# axiom_beta_plugin_module_TE0714_SDI_v0_5.net
KiCad netlist of a schematic drawn in EAGLE
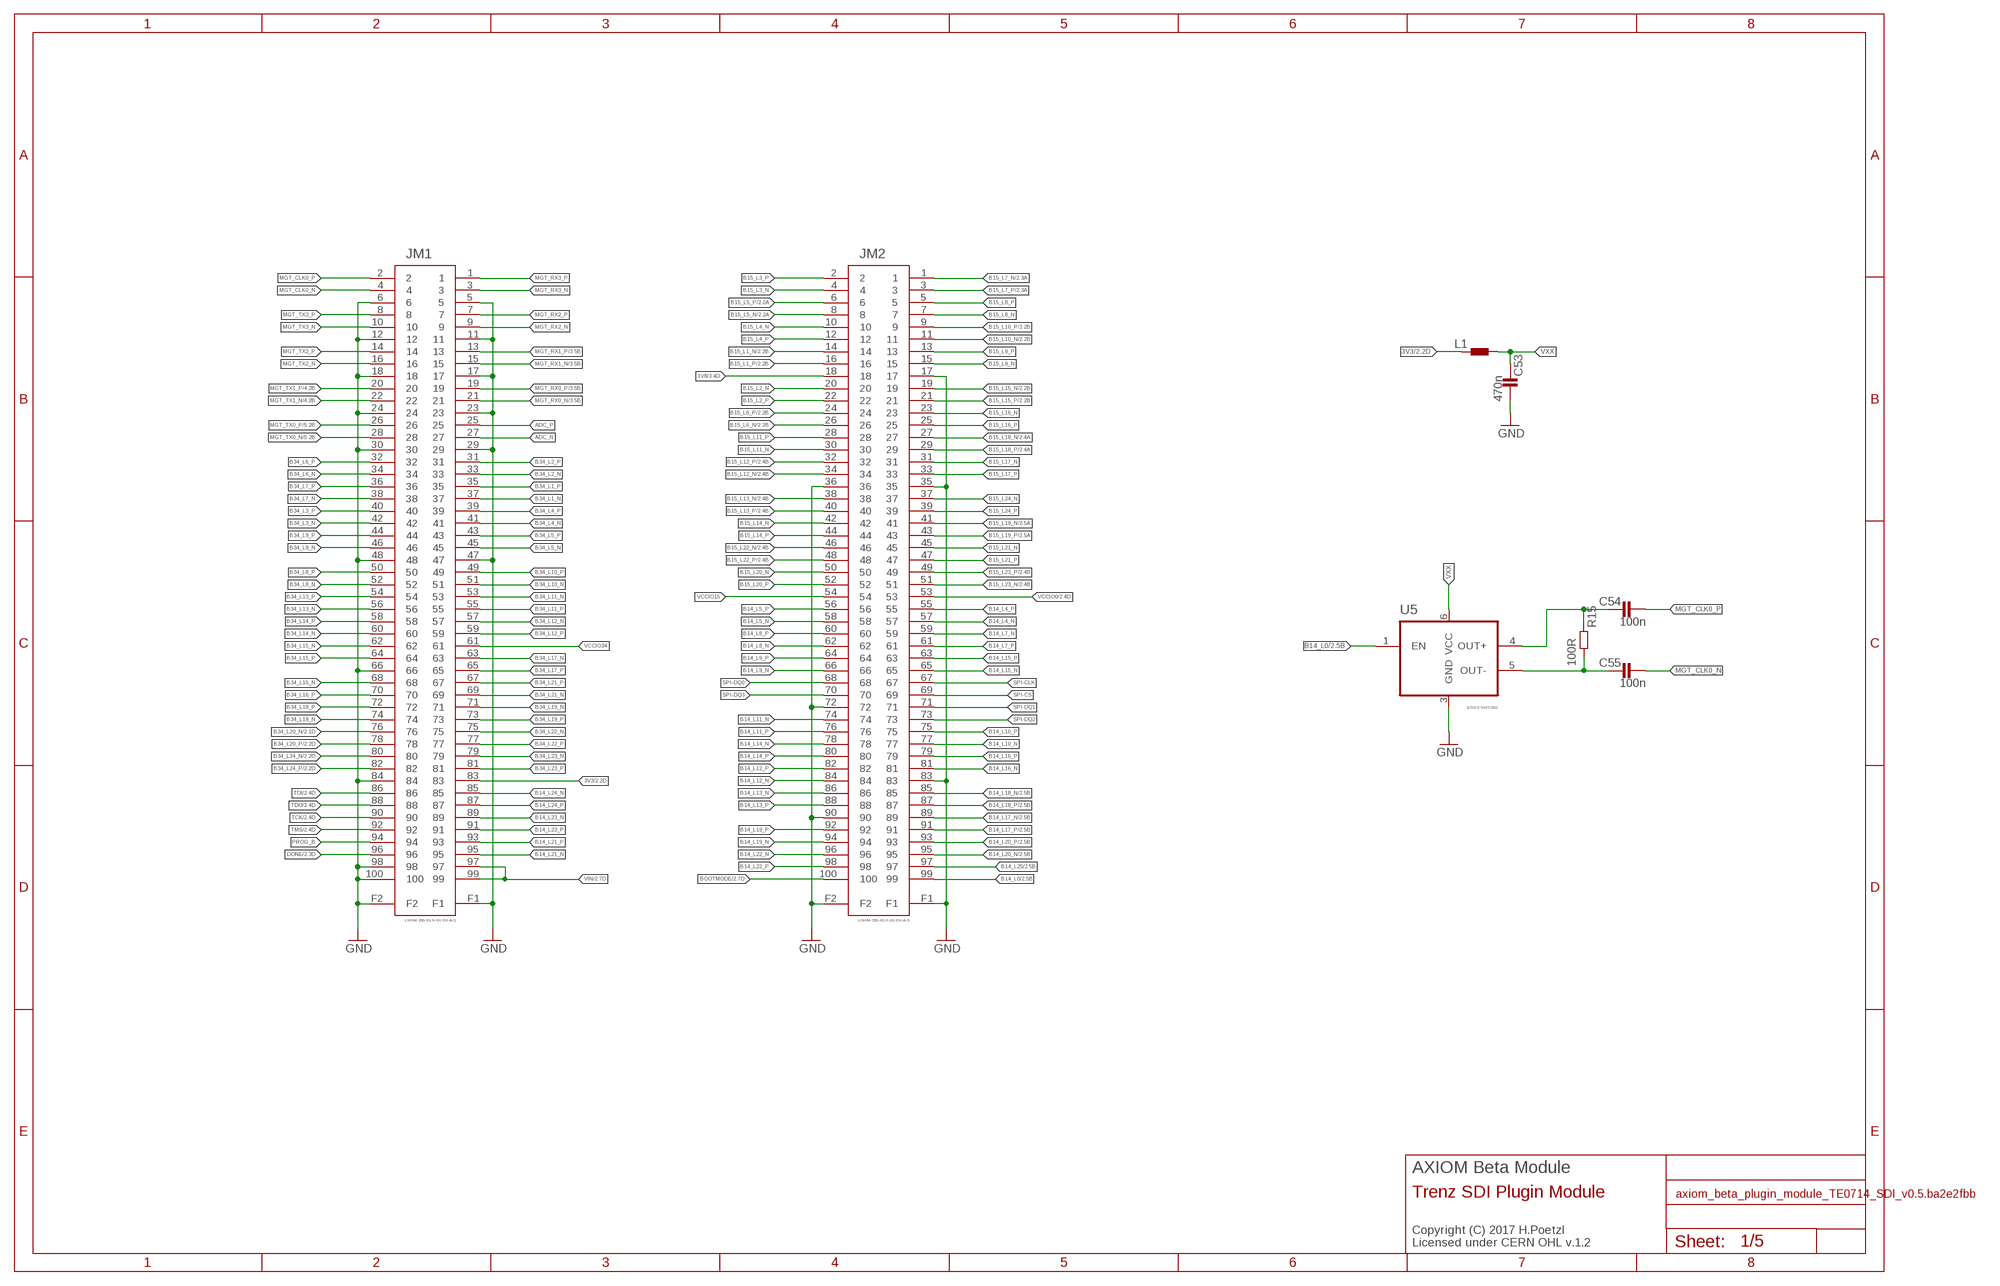
[diagram p0: schematic, sheet 1]
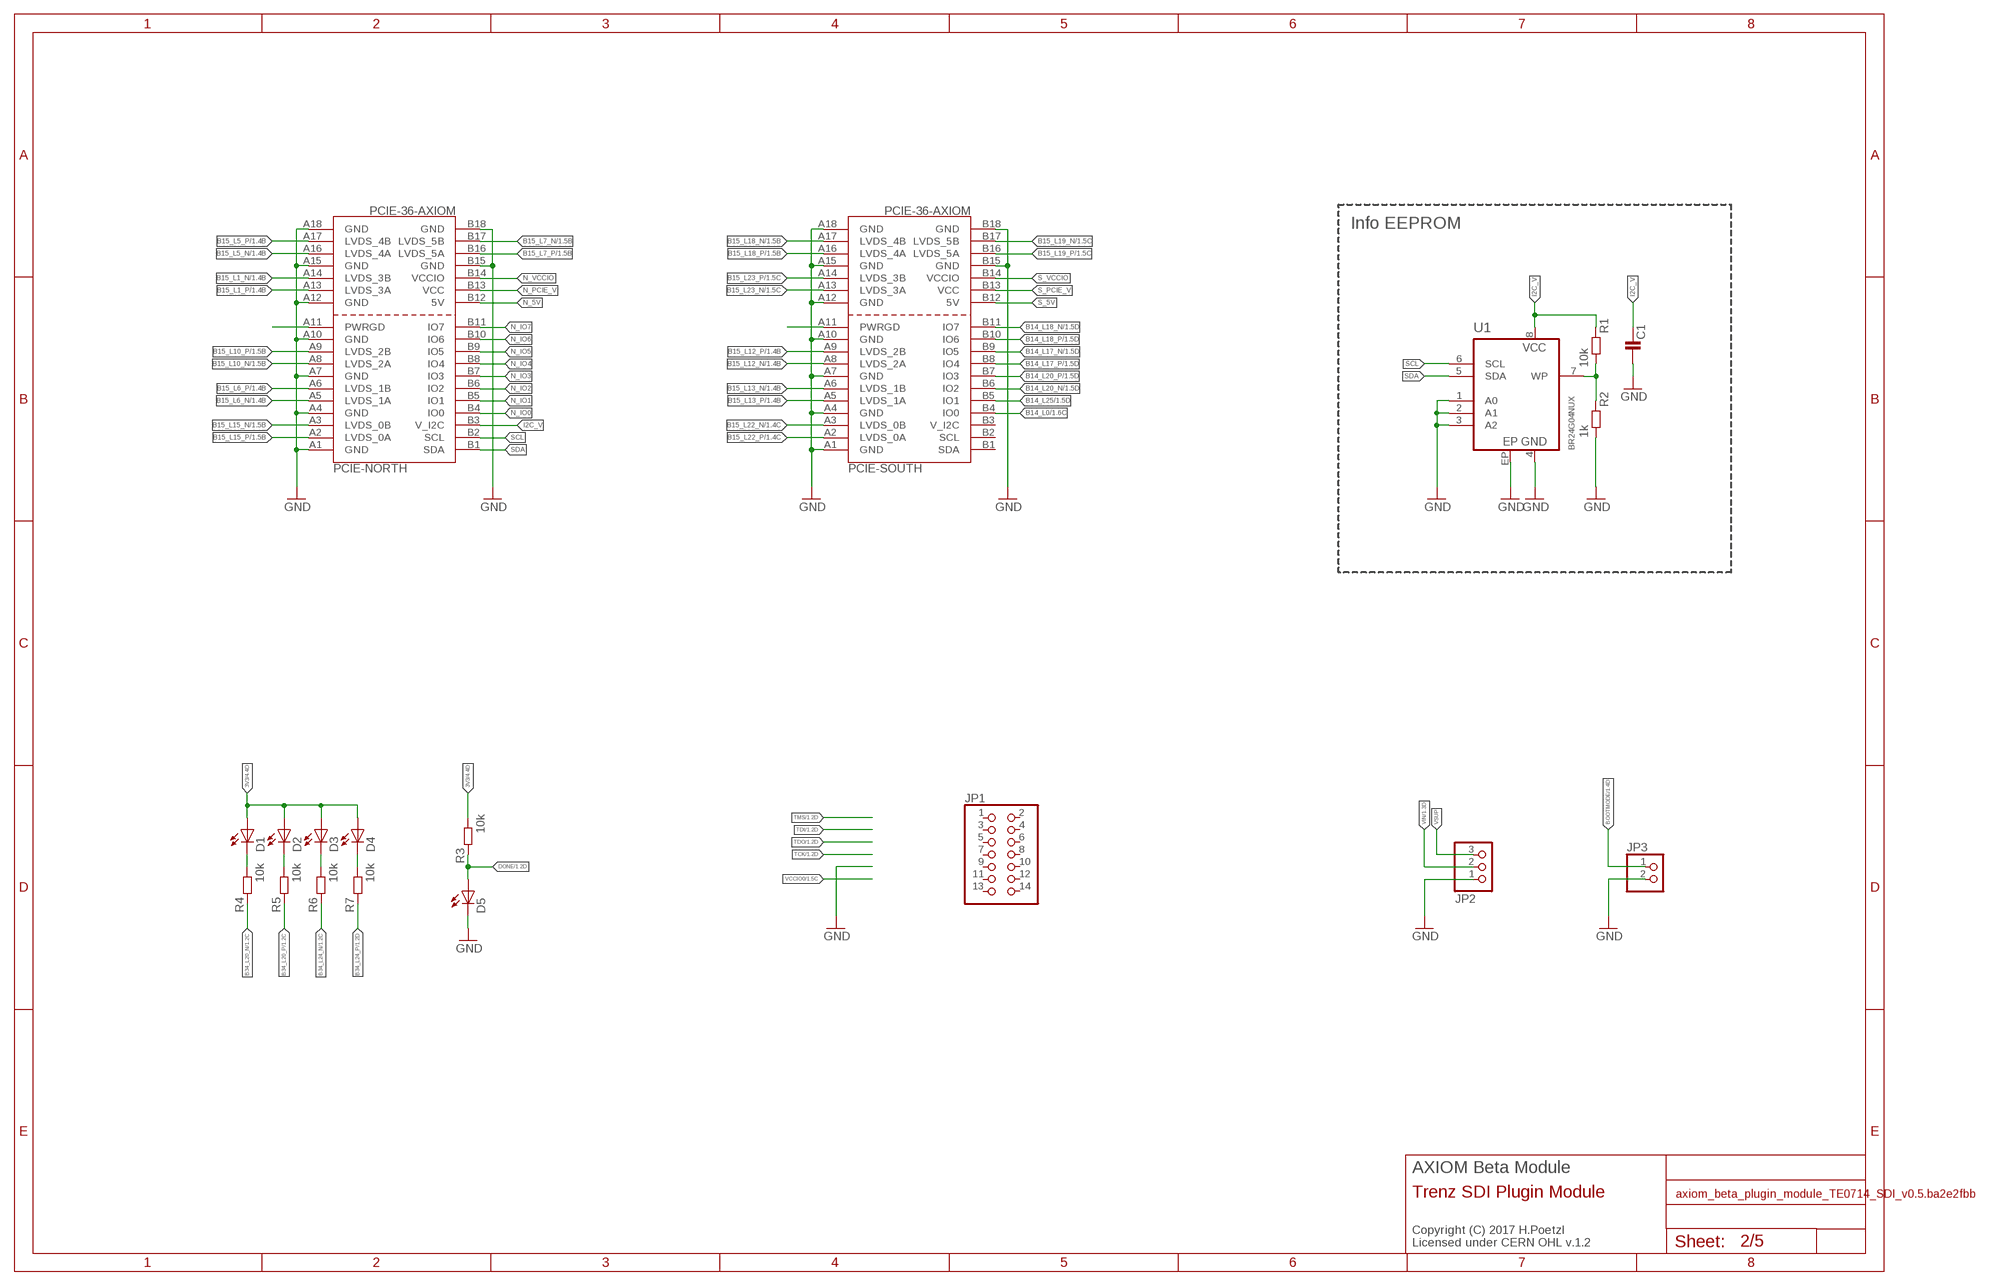
[diagram p1: schematic, sheet 2]
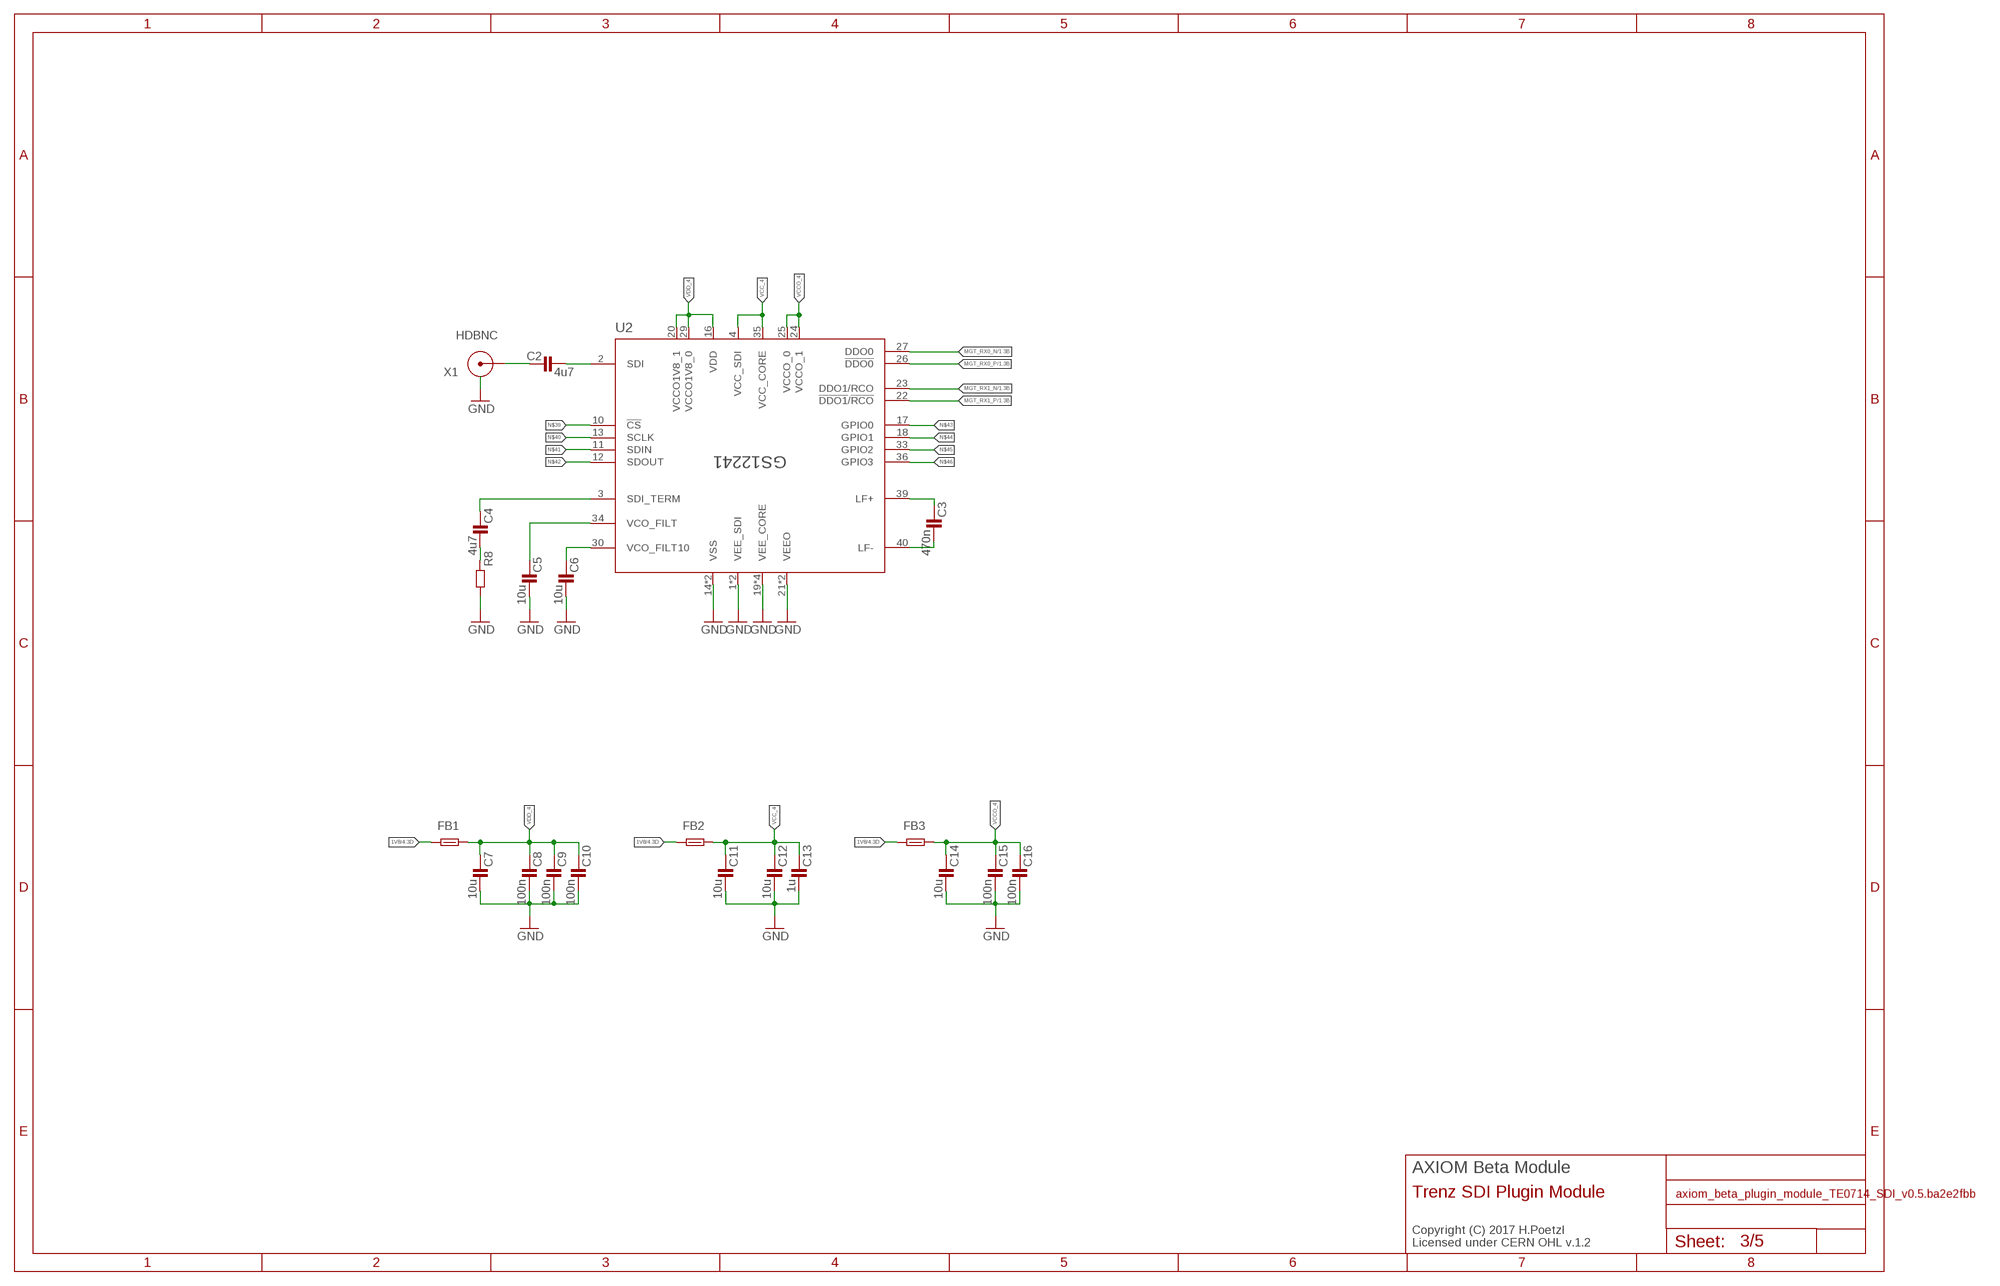
[diagram p2: schematic, sheet 3]
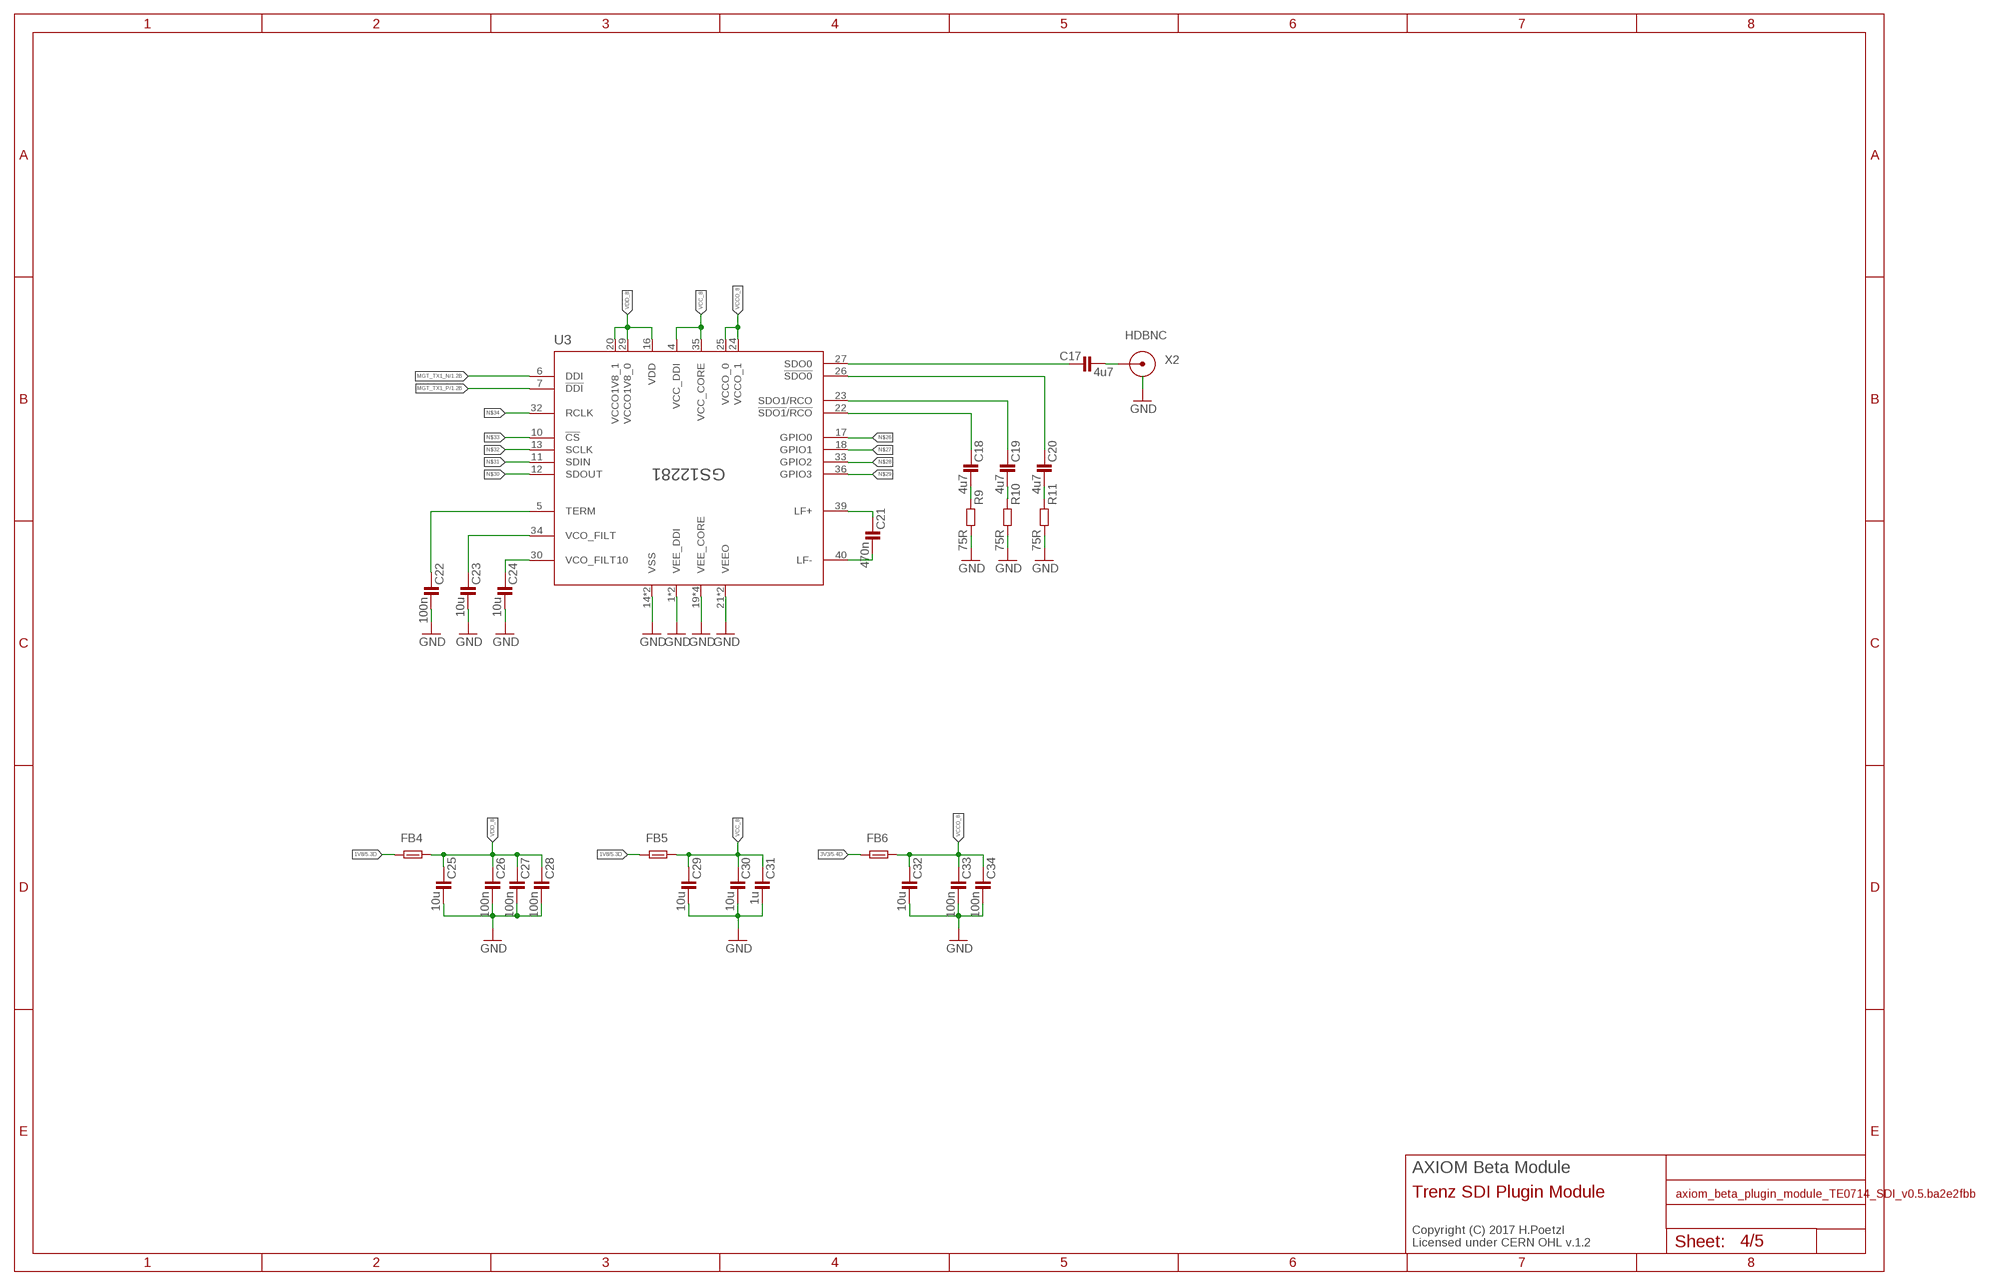
[diagram p3: schematic, sheet 4]
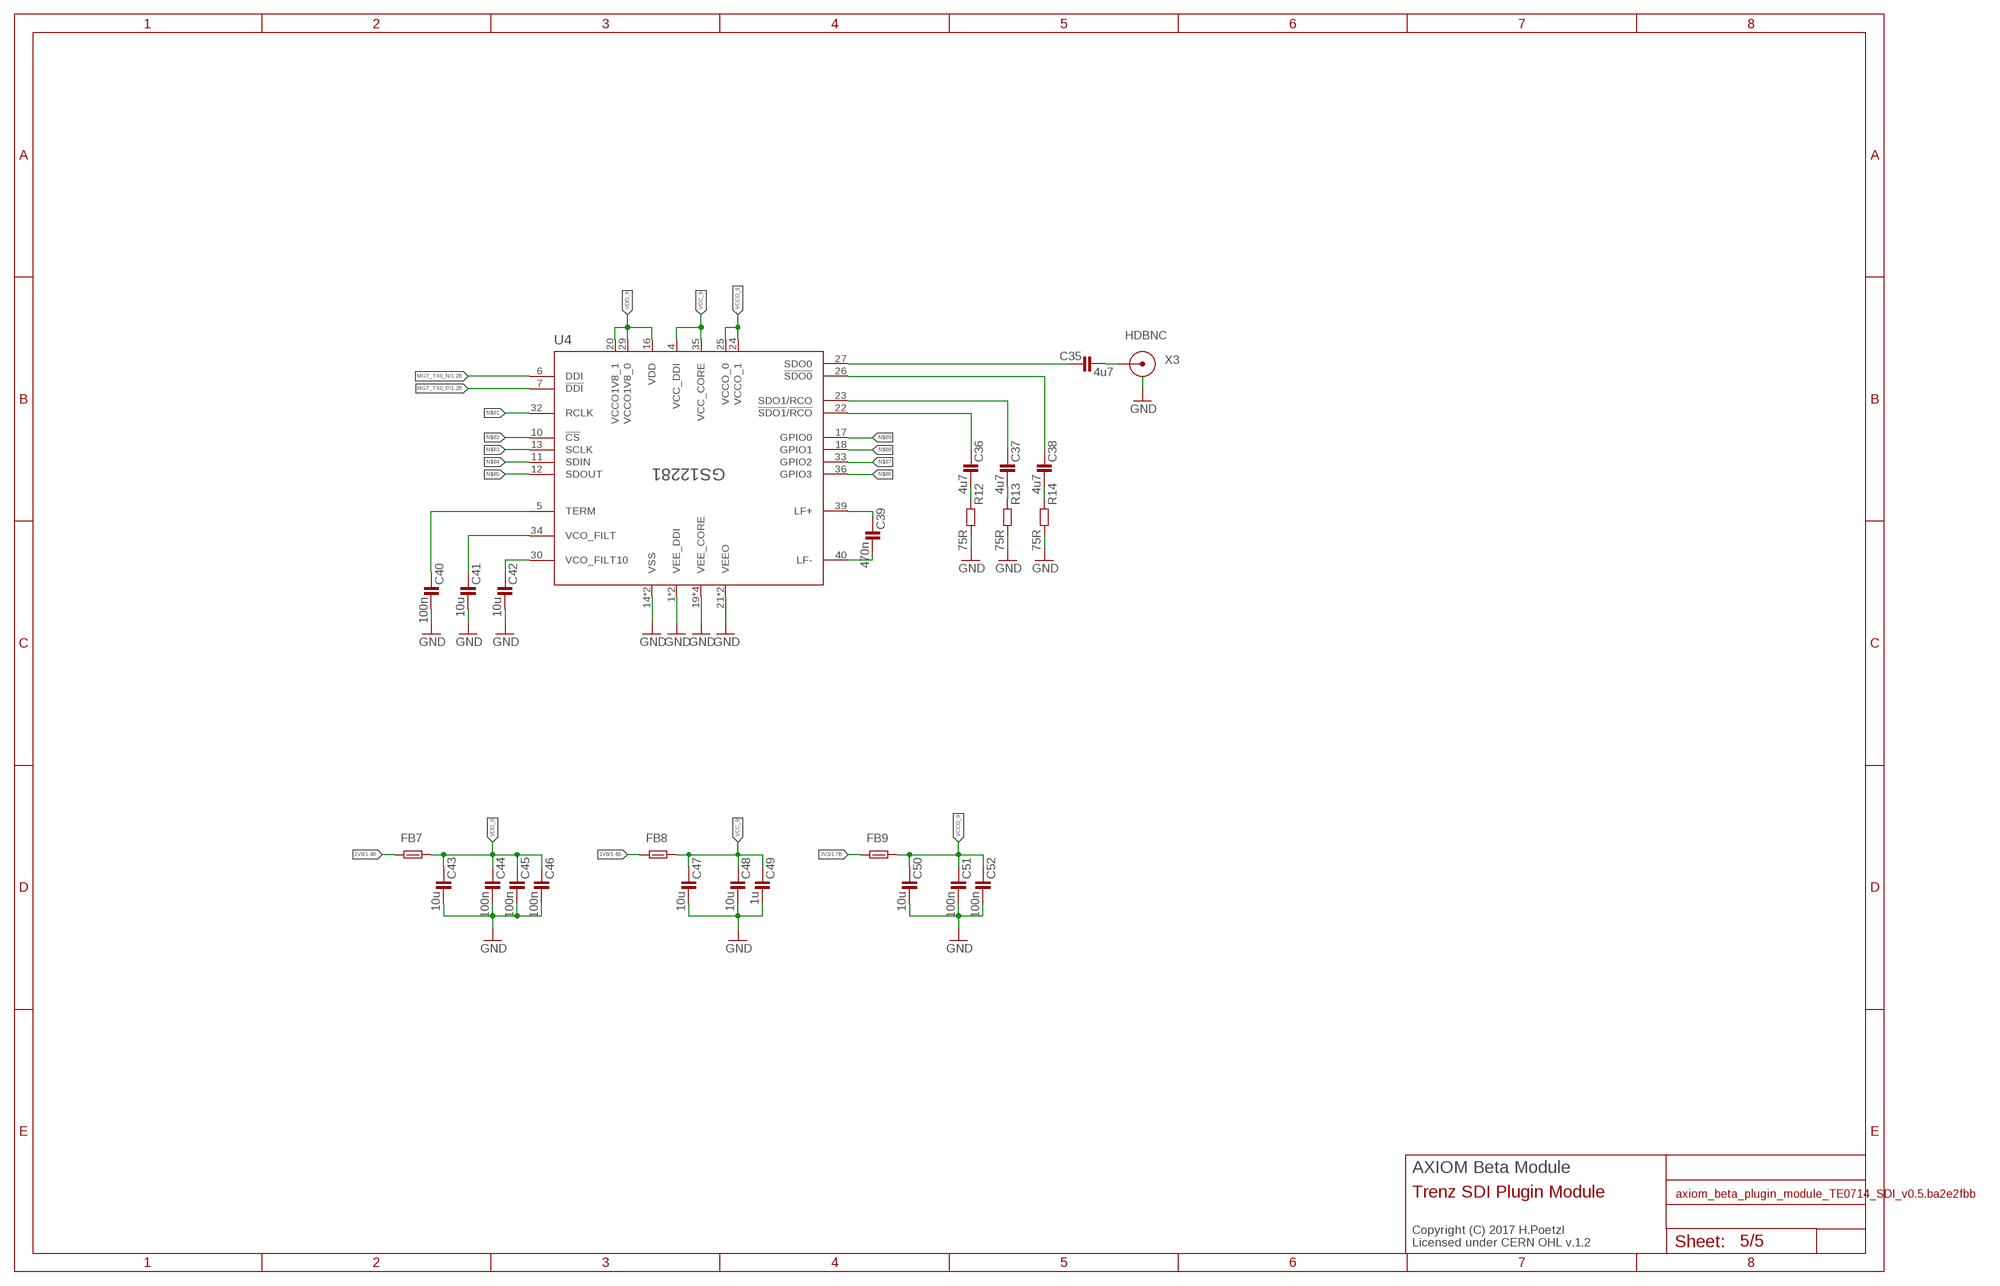
[diagram p4: schematic, sheet 5]

(export (version "E")
  (design (tool "Eeschema 10.0.6"))
  (components
    (comp (ref "C2")
      (value "4u7")
      (footprint "eagle-import:0402-C")
      (libsource (lib "eagle-import") (part "C0402-C"))
    )
    (comp (ref "C3")
      (value "470n")
      (footprint "eagle-import:0201-C")
      (libsource (lib "eagle-import") (part "C0201-C"))
    )
    (comp (ref "C4")
      (value "4u7")
      (footprint "eagle-import:0201-C")
      (libsource (lib "eagle-import") (part "C0201-C"))
    )
    (comp (ref "C5")
      (value "10u")
      (footprint "eagle-import:0201-C")
      (libsource (lib "eagle-import") (part "C0201-C"))
    )
    (comp (ref "C6")
      (value "10u")
      (footprint "eagle-import:0201-C")
      (libsource (lib "eagle-import") (part "C0201-C"))
    )
    (comp (ref "C7")
      (value "10u")
      (footprint "eagle-import:0402-C")
      (libsource (lib "eagle-import") (part "C0402-C"))
    )
    (comp (ref "C8")
      (value "100n")
      (footprint "eagle-import:0201-C")
      (libsource (lib "eagle-import") (part "C0201-C"))
    )
    (comp (ref "C9")
      (value "100n")
      (footprint "eagle-import:0201-C")
      (libsource (lib "eagle-import") (part "C0201-C"))
    )
    (comp (ref "C10")
      (value "100n")
      (footprint "eagle-import:0201-C")
      (libsource (lib "eagle-import") (part "C0201-C"))
    )
    (comp (ref "C11")
      (value "10u")
      (footprint "eagle-import:0402-C")
      (libsource (lib "eagle-import") (part "C0402-C"))
    )
    (comp (ref "C12")
      (value "10u")
      (footprint "eagle-import:0201-C")
      (libsource (lib "eagle-import") (part "C0201-C"))
    )
    (comp (ref "C13")
      (value "1u")
      (footprint "eagle-import:0201-C")
      (libsource (lib "eagle-import") (part "C0201-C"))
    )
    (comp (ref "C14")
      (value "10u")
      (footprint "eagle-import:0402-C")
      (libsource (lib "eagle-import") (part "C0402-C"))
    )
    (comp (ref "C15")
      (value "100n")
      (footprint "eagle-import:0201-C")
      (libsource (lib "eagle-import") (part "C0201-C"))
    )
    (comp (ref "C16")
      (value "100n")
      (footprint "eagle-import:0201-C")
      (libsource (lib "eagle-import") (part "C0201-C"))
    )
    (comp (ref "FB1")
      (value "FB0402-C")
      (footprint "eagle-import:0402-C")
      (libsource (lib "eagle-import") (part "FB0402-C"))
    )
    (comp (ref "FB2")
      (value "FB0402-C")
      (footprint "eagle-import:0402-C")
      (libsource (lib "eagle-import") (part "FB0402-C"))
    )
    (comp (ref "FB3")
      (value "FB0402-C")
      (footprint "eagle-import:0402-C")
      (libsource (lib "eagle-import") (part "FB0402-C"))
    )
    (comp (ref "R8")
      (value "R0201-C")
      (footprint "eagle-import:0201-C")
      (libsource (lib "eagle-import") (part "R0201-C"))
    )
    (comp (ref "U2")
      (value "GS12241")
      (footprint "eagle-import:UQFN40P600X400X100-41N")
      (libsource (lib "eagle-import") (part "GS12241"))
    )
    (comp (ref "X1")
      (value "HDBNC")
      (footprint "eagle-import:HDBNC_EDGE_2SIDE")
      (libsource (lib "eagle-import") (part "HDBNC"))
    )
    (comp (ref "C53")
      (value "470n")
      (footprint "eagle-import:0402-C")
      (libsource (lib "eagle-import") (part "C0402-C"))
    )
    (comp (ref "C54")
      (value "100n")
      (footprint "eagle-import:0201-C")
      (libsource (lib "eagle-import") (part "C0201-C"))
    )
    (comp (ref "C55")
      (value "100n")
      (footprint "eagle-import:0201-C")
      (libsource (lib "eagle-import") (part "C0201-C"))
    )
    (comp (ref "JM1")
      (value "LSHM-150-XX.X-XX-DV-A-S")
      (footprint "eagle-import:LSHM-150-XX.X-XX-DV-A-S")
      (libsource (lib "eagle-import") (part "LSHM-150-XX.X-XX-DV-A-S"))
    )
    (comp (ref "JM2")
      (value "LSHM-150-XX.X-XX-DV-A-S")
      (footprint "eagle-import:LSHM-150-XX.X-XX-DV-A-S")
      (libsource (lib "eagle-import") (part "LSHM-150-XX.X-XX-DV-A-S"))
    )
    (comp (ref "L1")
      (value "L0402-C")
      (footprint "eagle-import:0402-C")
      (libsource (lib "eagle-import") (part "L0402-C"))
    )
    (comp (ref "R15")
      (value "100R")
      (footprint "eagle-import:0201-C")
      (libsource (lib "eagle-import") (part "R0201-C"))
    )
    (comp (ref "U5")
      (value "DSC11XX-3.2X2.5")
      (footprint "eagle-import:3.2X2.5")
      (libsource (lib "eagle-import") (part "DSC11XX-3.2X2.5"))
    )
    (comp (ref "C1")
      (value "C0402-B")
      (footprint "eagle-import:0402-B")
      (libsource (lib "eagle-import") (part "C0402-B"))
    )
    (comp (ref "D1")
      (value "LED")
      (footprint "eagle-import:SMARTLED-TTW")
      (libsource (lib "eagle-import") (part "LED"))
    )
    (comp (ref "D2")
      (value "LED")
      (footprint "eagle-import:SMARTLED-TTW")
      (libsource (lib "eagle-import") (part "LED"))
    )
    (comp (ref "D3")
      (value "LED")
      (footprint "eagle-import:SMARTLED-TTW")
      (libsource (lib "eagle-import") (part "LED"))
    )
    (comp (ref "D4")
      (value "LED")
      (footprint "eagle-import:SMARTLED-TTW")
      (libsource (lib "eagle-import") (part "LED"))
    )
    (comp (ref "D5")
      (value "LED")
      (footprint "eagle-import:SMARTLED-TTW")
      (libsource (lib "eagle-import") (part "LED"))
    )
    (comp (ref "JP1")
      (value "PINHD-2X07_2.00")
      (footprint "eagle-import:2X07M")
      (libsource (lib "eagle-import") (part "PINHD-2X07_2.00"))
    )
    (comp (ref "JP2")
      (value "PINHD-1X03_2.54-90°-S")
      (footprint "eagle-import:1X03_90-S")
      (libsource (lib "eagle-import") (part "PINHD-1X03_2.54-90°-S"))
    )
    (comp (ref "JP3")
      (value "PINHD-1X02_2.54-S")
      (footprint "eagle-import:1X02-S")
      (libsource (lib "eagle-import") (part "PINHD-1X02_2.54-S"))
    )
    (comp (ref "PCIE-NORTH")
      (value "PCIE-36-AXIOM")
      (footprint "eagle-import:PCIE-36-AXIOM")
      (libsource (lib "eagle-import") (part "PCIE-36-AXIOM"))
    )
    (comp (ref "PCIE-SOUTH")
      (value "PCIE-36-AXIOM")
      (footprint "eagle-import:PCIE-36-AXIOM")
      (libsource (lib "eagle-import") (part "PCIE-36-AXIOM"))
    )
    (comp (ref "R1")
      (value "10k")
      (footprint "eagle-import:0402-B")
      (libsource (lib "eagle-import") (part "R0402-B"))
    )
    (comp (ref "R2")
      (value "1k")
      (footprint "eagle-import:0402-B")
      (libsource (lib "eagle-import") (part "R0402-B"))
    )
    (comp (ref "R3")
      (value "10k")
      (footprint "eagle-import:0402-C")
      (libsource (lib "eagle-import") (part "R0402-C"))
    )
    (comp (ref "R4")
      (value "10k")
      (footprint "eagle-import:0402-C")
      (libsource (lib "eagle-import") (part "R0402-C"))
    )
    (comp (ref "R5")
      (value "10k")
      (footprint "eagle-import:0402-C")
      (libsource (lib "eagle-import") (part "R0402-C"))
    )
    (comp (ref "R6")
      (value "10k")
      (footprint "eagle-import:0402-C")
      (libsource (lib "eagle-import") (part "R0402-C"))
    )
    (comp (ref "R7")
      (value "10k")
      (footprint "eagle-import:0402-C")
      (libsource (lib "eagle-import") (part "R0402-C"))
    )
    (comp (ref "U1")
      (value "BR24G04NUX")
      (footprint "eagle-import:DFN200X300X100-9N")
      (libsource (lib "eagle-import") (part "BR24G04NUX"))
    )
    (comp (ref "C35")
      (value "4u7")
      (footprint "eagle-import:0402-C")
      (libsource (lib "eagle-import") (part "C0402-C"))
    )
    (comp (ref "C36")
      (value "4u7")
      (footprint "eagle-import:0201-C")
      (libsource (lib "eagle-import") (part "C0201-C"))
    )
    (comp (ref "C37")
      (value "4u7")
      (footprint "eagle-import:0201-C")
      (libsource (lib "eagle-import") (part "C0201-C"))
    )
    (comp (ref "C38")
      (value "4u7")
      (footprint "eagle-import:0201-C")
      (libsource (lib "eagle-import") (part "C0201-C"))
    )
    (comp (ref "C39")
      (value "470n")
      (footprint "eagle-import:0201-C")
      (libsource (lib "eagle-import") (part "C0201-C"))
    )
    (comp (ref "C40")
      (value "100n")
      (footprint "eagle-import:0201-C")
      (libsource (lib "eagle-import") (part "C0201-C"))
    )
    (comp (ref "C41")
      (value "10u")
      (footprint "eagle-import:0201-C")
      (libsource (lib "eagle-import") (part "C0201-C"))
    )
    (comp (ref "C42")
      (value "10u")
      (footprint "eagle-import:0201-C")
      (libsource (lib "eagle-import") (part "C0201-C"))
    )
    (comp (ref "C43")
      (value "10u")
      (footprint "eagle-import:0402-C")
      (libsource (lib "eagle-import") (part "C0402-C"))
    )
    (comp (ref "C44")
      (value "100n")
      (footprint "eagle-import:0201-C")
      (libsource (lib "eagle-import") (part "C0201-C"))
    )
    (comp (ref "C45")
      (value "100n")
      (footprint "eagle-import:0201-C")
      (libsource (lib "eagle-import") (part "C0201-C"))
    )
    (comp (ref "C46")
      (value "100n")
      (footprint "eagle-import:0201-C")
      (libsource (lib "eagle-import") (part "C0201-C"))
    )
    (comp (ref "C47")
      (value "10u")
      (footprint "eagle-import:0402-C")
      (libsource (lib "eagle-import") (part "C0402-C"))
    )
    (comp (ref "C48")
      (value "10u")
      (footprint "eagle-import:0201-C")
      (libsource (lib "eagle-import") (part "C0201-C"))
    )
    (comp (ref "C49")
      (value "1u")
      (footprint "eagle-import:0201-C")
      (libsource (lib "eagle-import") (part "C0201-C"))
    )
    (comp (ref "C50")
      (value "10u")
      (footprint "eagle-import:0402-C")
      (libsource (lib "eagle-import") (part "C0402-C"))
    )
    (comp (ref "C51")
      (value "100n")
      (footprint "eagle-import:0201-C")
      (libsource (lib "eagle-import") (part "C0201-C"))
    )
    (comp (ref "C52")
      (value "100n")
      (footprint "eagle-import:0201-C")
      (libsource (lib "eagle-import") (part "C0201-C"))
    )
    (comp (ref "FB7")
      (value "FB0402-C")
      (footprint "eagle-import:0402-C")
      (libsource (lib "eagle-import") (part "FB0402-C"))
    )
    (comp (ref "FB8")
      (value "FB0402-C")
      (footprint "eagle-import:0402-C")
      (libsource (lib "eagle-import") (part "FB0402-C"))
    )
    (comp (ref "FB9")
      (value "FB0402-C")
      (footprint "eagle-import:0402-C")
      (libsource (lib "eagle-import") (part "FB0402-C"))
    )
    (comp (ref "R12")
      (value "75R")
      (footprint "eagle-import:0201-C")
      (libsource (lib "eagle-import") (part "R0201-C"))
    )
    (comp (ref "R13")
      (value "75R")
      (footprint "eagle-import:0201-C")
      (libsource (lib "eagle-import") (part "R0201-C"))
    )
    (comp (ref "R14")
      (value "75R")
      (footprint "eagle-import:0201-C")
      (libsource (lib "eagle-import") (part "R0201-C"))
    )
    (comp (ref "U4")
      (value "GS12281")
      (footprint "eagle-import:UQFN40P600X400X100-41N")
      (libsource (lib "eagle-import") (part "GS12281"))
    )
    (comp (ref "X3")
      (value "HDBNC")
      (footprint "eagle-import:HDBNC_EDGE_2SIDE")
      (libsource (lib "eagle-import") (part "HDBNC"))
    )
    (comp (ref "C17")
      (value "4u7")
      (footprint "eagle-import:0402-C")
      (libsource (lib "eagle-import") (part "C0402-C"))
    )
    (comp (ref "C18")
      (value "4u7")
      (footprint "eagle-import:0201-C")
      (libsource (lib "eagle-import") (part "C0201-C"))
    )
    (comp (ref "C19")
      (value "4u7")
      (footprint "eagle-import:0201-C")
      (libsource (lib "eagle-import") (part "C0201-C"))
    )
    (comp (ref "C20")
      (value "4u7")
      (footprint "eagle-import:0201-C")
      (libsource (lib "eagle-import") (part "C0201-C"))
    )
    (comp (ref "C21")
      (value "470n")
      (footprint "eagle-import:0201-C")
      (libsource (lib "eagle-import") (part "C0201-C"))
    )
    (comp (ref "C22")
      (value "100n")
      (footprint "eagle-import:0201-C")
      (libsource (lib "eagle-import") (part "C0201-C"))
    )
    (comp (ref "C23")
      (value "10u")
      (footprint "eagle-import:0201-C")
      (libsource (lib "eagle-import") (part "C0201-C"))
    )
    (comp (ref "C24")
      (value "10u")
      (footprint "eagle-import:0201-C")
      (libsource (lib "eagle-import") (part "C0201-C"))
    )
    (comp (ref "C25")
      (value "10u")
      (footprint "eagle-import:0402-C")
      (libsource (lib "eagle-import") (part "C0402-C"))
    )
    (comp (ref "C26")
      (value "100n")
      (footprint "eagle-import:0201-C")
      (libsource (lib "eagle-import") (part "C0201-C"))
    )
    (comp (ref "C27")
      (value "100n")
      (footprint "eagle-import:0201-C")
      (libsource (lib "eagle-import") (part "C0201-C"))
    )
    (comp (ref "C28")
      (value "100n")
      (footprint "eagle-import:0201-C")
      (libsource (lib "eagle-import") (part "C0201-C"))
    )
    (comp (ref "C29")
      (value "10u")
      (footprint "eagle-import:0402-C")
      (libsource (lib "eagle-import") (part "C0402-C"))
    )
    (comp (ref "C30")
      (value "10u")
      (footprint "eagle-import:0201-C")
      (libsource (lib "eagle-import") (part "C0201-C"))
    )
    (comp (ref "C31")
      (value "1u")
      (footprint "eagle-import:0201-C")
      (libsource (lib "eagle-import") (part "C0201-C"))
    )
    (comp (ref "C32")
      (value "10u")
      (footprint "eagle-import:0402-C")
      (libsource (lib "eagle-import") (part "C0402-C"))
    )
    (comp (ref "C33")
      (value "100n")
      (footprint "eagle-import:0201-C")
      (libsource (lib "eagle-import") (part "C0201-C"))
    )
    (comp (ref "C34")
      (value "100n")
      (footprint "eagle-import:0201-C")
      (libsource (lib "eagle-import") (part "C0201-C"))
    )
    (comp (ref "FB4")
      (value "FB0402-C")
      (footprint "eagle-import:0402-C")
      (libsource (lib "eagle-import") (part "FB0402-C"))
    )
    (comp (ref "FB5")
      (value "FB0402-C")
      (footprint "eagle-import:0402-C")
      (libsource (lib "eagle-import") (part "FB0402-C"))
    )
    (comp (ref "FB6")
      (value "FB0402-C")
      (footprint "eagle-import:0402-C")
      (libsource (lib "eagle-import") (part "FB0402-C"))
    )
    (comp (ref "R9")
      (value "75R")
      (footprint "eagle-import:0201-C")
      (libsource (lib "eagle-import") (part "R0201-C"))
    )
    (comp (ref "R10")
      (value "75R")
      (footprint "eagle-import:0201-C")
      (libsource (lib "eagle-import") (part "R0201-C"))
    )
    (comp (ref "R11")
      (value "75R")
      (footprint "eagle-import:0201-C")
      (libsource (lib "eagle-import") (part "R0201-C"))
    )
    (comp (ref "U3")
      (value "GS12281")
      (footprint "eagle-import:UQFN40P600X400X100-41N")
      (libsource (lib "eagle-import") (part "GS12281"))
    )
    (comp (ref "X2")
      (value "HDBNC")
      (footprint "eagle-import:HDBNC_EDGE_2SIDE")
      (libsource (lib "eagle-import") (part "HDBNC"))
    )
  )
  (nets
    (net (code "1") (name "1V8") (class "Default")
      (node (ref "FB1") (pin "1") (pinfunction "1_1") (pintype "passive"))
      (node (ref "FB2") (pin "1") (pinfunction "1_1") (pintype "passive"))
      (node (ref "FB3") (pin "1") (pinfunction "1_1") (pintype "passive"))
      (node (ref "FB4") (pin "1") (pinfunction "1_1") (pintype "passive"))
      (node (ref "FB5") (pin "1") (pinfunction "1_1") (pintype "passive"))
      (node (ref "FB7") (pin "1") (pinfunction "1_1") (pintype "passive"))
      (node (ref "FB8") (pin "1") (pinfunction "1_1") (pintype "passive"))
      (node (ref "JM2") (pin "18") (pinfunction "18_18") (pintype "bidirectional"))
    )
    (net (code "2") (name "3V3") (class "Default")
      (node (ref "D1") (pin "A@1") (pinfunction "A_A@1") (pintype "passive"))
      (node (ref "D2") (pin "A@1") (pinfunction "A_A@1") (pintype "passive"))
      (node (ref "D3") (pin "A@1") (pinfunction "A_A@1") (pintype "passive"))
      (node (ref "D4") (pin "A@1") (pinfunction "A_A@1") (pintype "passive"))
      (node (ref "FB6") (pin "1") (pinfunction "1_1") (pintype "passive"))
      (node (ref "FB9") (pin "1") (pinfunction "1_1") (pintype "passive"))
      (node (ref "JM1") (pin "83") (pinfunction "83_83") (pintype "bidirectional"))
      (node (ref "L1") (pin "1") (pinfunction "1_1") (pintype "passive"))
      (node (ref "R3") (pin "2") (pinfunction "2_2") (pintype "passive"))
    )
    (net (code "3") (name "ADC_N") (class "Default")
      (node (ref "JM1") (pin "27") (pinfunction "27_27") (pintype "bidirectional"))
    )
    (net (code "4") (name "ADC_P") (class "Default")
      (node (ref "JM1") (pin "25") (pinfunction "25_25") (pintype "bidirectional"))
    )
    (net (code "5") (name "B14_L0") (class "Default")
      (node (ref "JM2") (pin "99") (pinfunction "99_99") (pintype "bidirectional"))
      (node (ref "PCIE-SOUTH") (pin "B4") (pinfunction "IO0_B4") (pintype "passive"))
      (node (ref "U5") (pin "1") (pinfunction "EN_1") (pintype "input"))
    )
    (net (code "6") (name "B14_L4_N") (class "Default")
      (node (ref "JM2") (pin "57") (pinfunction "57_57") (pintype "bidirectional"))
    )
    (net (code "7") (name "B14_L4_P") (class "Default")
      (node (ref "JM2") (pin "55") (pinfunction "55_55") (pintype "bidirectional"))
    )
    (net (code "8") (name "B14_L5_N") (class "Default")
      (node (ref "JM2") (pin "58") (pinfunction "58_58") (pintype "bidirectional"))
    )
    (net (code "9") (name "B14_L5_P") (class "Default")
      (node (ref "JM2") (pin "56") (pinfunction "56_56") (pintype "bidirectional"))
    )
    (net (code "10") (name "B14_L7_N") (class "Default")
      (node (ref "JM2") (pin "59") (pinfunction "59_59") (pintype "bidirectional"))
    )
    (net (code "11") (name "B14_L7_P") (class "Default")
      (node (ref "JM2") (pin "61") (pinfunction "61_61") (pintype "bidirectional"))
    )
    (net (code "12") (name "B14_L8_N") (class "Default")
      (node (ref "JM2") (pin "62") (pinfunction "62_62") (pintype "bidirectional"))
    )
    (net (code "13") (name "B14_L8_P") (class "Default")
      (node (ref "JM2") (pin "60") (pinfunction "60_60") (pintype "bidirectional"))
    )
    (net (code "14") (name "B14_L9_N") (class "Default")
      (node (ref "JM2") (pin "66") (pinfunction "66_66") (pintype "bidirectional"))
    )
    (net (code "15") (name "B14_L9_P") (class "Default")
      (node (ref "JM2") (pin "64") (pinfunction "64_64") (pintype "bidirectional"))
    )
    (net (code "16") (name "B14_L10_N") (class "Default")
      (node (ref "JM2") (pin "77") (pinfunction "77_77") (pintype "bidirectional"))
    )
    (net (code "17") (name "B14_L10_P") (class "Default")
      (node (ref "JM2") (pin "75") (pinfunction "75_75") (pintype "bidirectional"))
    )
    (net (code "18") (name "B14_L11_N") (class "Default")
      (node (ref "JM2") (pin "74") (pinfunction "74_74") (pintype "bidirectional"))
    )
    (net (code "19") (name "B14_L11_P") (class "Default")
      (node (ref "JM2") (pin "76") (pinfunction "76_76") (pintype "bidirectional"))
    )
    (net (code "20") (name "B14_L12_N") (class "Default")
      (node (ref "JM2") (pin "84") (pinfunction "84_84") (pintype "bidirectional"))
    )
    (net (code "21") (name "B14_L12_P") (class "Default")
      (node (ref "JM2") (pin "82") (pinfunction "82_82") (pintype "bidirectional"))
    )
    (net (code "22") (name "B14_L13_N") (class "Default")
      (node (ref "JM2") (pin "86") (pinfunction "86_86") (pintype "bidirectional"))
    )
    (net (code "23") (name "B14_L13_P") (class "Default")
      (node (ref "JM2") (pin "88") (pinfunction "88_88") (pintype "bidirectional"))
    )
    (net (code "24") (name "B14_L14_N") (class "Default")
      (node (ref "JM2") (pin "78") (pinfunction "78_78") (pintype "bidirectional"))
    )
    (net (code "25") (name "B14_L14_P") (class "Default")
      (node (ref "JM2") (pin "80") (pinfunction "80_80") (pintype "bidirectional"))
    )
    (net (code "26") (name "B14_L15_N") (class "Default")
      (node (ref "JM2") (pin "65") (pinfunction "65_65") (pintype "bidirectional"))
    )
    (net (code "27") (name "B14_L15_P") (class "Default")
      (node (ref "JM2") (pin "63") (pinfunction "63_63") (pintype "bidirectional"))
    )
    (net (code "28") (name "B14_L16_N") (class "Default")
      (node (ref "JM2") (pin "81") (pinfunction "81_81") (pintype "bidirectional"))
    )
    (net (code "29") (name "B14_L16_P") (class "Default")
      (node (ref "JM2") (pin "79") (pinfunction "79_79") (pintype "bidirectional"))
    )
    (net (code "30") (name "B14_L17_N") (class "Default")
      (node (ref "JM2") (pin "89") (pinfunction "89_89") (pintype "bidirectional"))
      (node (ref "PCIE-SOUTH") (pin "B9") (pinfunction "IO5_B9") (pintype "passive"))
    )
    (net (code "31") (name "B14_L17_P") (class "Default")
      (node (ref "JM2") (pin "91") (pinfunction "91_91") (pintype "bidirectional"))
      (node (ref "PCIE-SOUTH") (pin "B8") (pinfunction "IO4_B8") (pintype "passive"))
    )
    (net (code "32") (name "B14_L18_N") (class "Default")
      (node (ref "JM2") (pin "85") (pinfunction "85_85") (pintype "bidirectional"))
      (node (ref "PCIE-SOUTH") (pin "B11") (pinfunction "IO7_B11") (pintype "passive"))
    )
    (net (code "33") (name "B14_L18_P") (class "Default")
      (node (ref "JM2") (pin "87") (pinfunction "87_87") (pintype "bidirectional"))
      (node (ref "PCIE-SOUTH") (pin "B10") (pinfunction "IO6_B10") (pintype "passive"))
    )
    (net (code "34") (name "B14_L19_N") (class "Default")
      (node (ref "JM2") (pin "94") (pinfunction "94_94") (pintype "bidirectional"))
    )
    (net (code "35") (name "B14_L19_P") (class "Default")
      (node (ref "JM2") (pin "92") (pinfunction "92_92") (pintype "bidirectional"))
    )
    (net (code "36") (name "B14_L20_N") (class "Default")
      (node (ref "JM2") (pin "95") (pinfunction "95_95") (pintype "bidirectional"))
      (node (ref "PCIE-SOUTH") (pin "B6") (pinfunction "IO2_B6") (pintype "passive"))
    )
    (net (code "37") (name "B14_L20_P") (class "Default")
      (node (ref "JM2") (pin "93") (pinfunction "93_93") (pintype "bidirectional"))
      (node (ref "PCIE-SOUTH") (pin "B7") (pinfunction "IO3_B7") (pintype "passive"))
    )
    (net (code "38") (name "B14_L21_N") (class "Default")
      (node (ref "JM1") (pin "95") (pinfunction "95_95") (pintype "bidirectional"))
    )
    (net (code "39") (name "B14_L21_P") (class "Default")
      (node (ref "JM1") (pin "93") (pinfunction "93_93") (pintype "bidirectional"))
    )
    (net (code "40") (name "B14_L22_N") (class "Default")
      (node (ref "JM2") (pin "96") (pinfunction "96_96") (pintype "bidirectional"))
    )
    (net (code "41") (name "B14_L22_P") (class "Default")
      (node (ref "JM2") (pin "98") (pinfunction "98_98") (pintype "bidirectional"))
    )
    (net (code "42") (name "B14_L23_N") (class "Default")
      (node (ref "JM1") (pin "89") (pinfunction "89_89") (pintype "bidirectional"))
    )
    (net (code "43") (name "B14_L23_P") (class "Default")
      (node (ref "JM1") (pin "91") (pinfunction "91_91") (pintype "bidirectional"))
    )
    (net (code "44") (name "B14_L24_N") (class "Default")
      (node (ref "JM1") (pin "85") (pinfunction "85_85") (pintype "bidirectional"))
    )
    (net (code "45") (name "B14_L24_P") (class "Default")
      (node (ref "JM1") (pin "87") (pinfunction "87_87") (pintype "bidirectional"))
    )
    (net (code "46") (name "B14_L25") (class "Default")
      (node (ref "JM2") (pin "97") (pinfunction "97_97") (pintype "bidirectional"))
      (node (ref "PCIE-SOUTH") (pin "B5") (pinfunction "IO1_B5") (pintype "passive"))
    )
    (net (code "47") (name "B15_L1_N") (class "Default")
      (node (ref "JM2") (pin "14") (pinfunction "14_14") (pintype "bidirectional"))
      (node (ref "PCIE-NORTH") (pin "A14") (pinfunction "LVDS_3B_A14") (pintype "passive"))
    )
    (net (code "48") (name "B15_L1_P") (class "Default")
      (node (ref "JM2") (pin "16") (pinfunction "16_16") (pintype "bidirectional"))
      (node (ref "PCIE-NORTH") (pin "A13") (pinfunction "LVDS_3A_A13") (pintype "passive"))
    )
    (net (code "49") (name "B15_L2_N") (class "Default")
      (node (ref "JM2") (pin "20") (pinfunction "20_20") (pintype "bidirectional"))
    )
    (net (code "50") (name "B15_L2_P") (class "Default")
      (node (ref "JM2") (pin "22") (pinfunction "22_22") (pintype "bidirectional"))
    )
    (net (code "51") (name "B15_L3_N") (class "Default")
      (node (ref "JM2") (pin "4") (pinfunction "4_4") (pintype "bidirectional"))
    )
    (net (code "52") (name "B15_L3_P") (class "Default")
      (node (ref "JM2") (pin "2") (pinfunction "2_2") (pintype "bidirectional"))
    )
    (net (code "53") (name "B15_L4_N") (class "Default")
      (node (ref "JM2") (pin "10") (pinfunction "10_10") (pintype "bidirectional"))
    )
    (net (code "54") (name "B15_L4_P") (class "Default")
      (node (ref "JM2") (pin "12") (pinfunction "12_12") (pintype "bidirectional"))
    )
    (net (code "55") (name "B15_L5_N") (class "Default")
      (node (ref "JM2") (pin "8") (pinfunction "8_8") (pintype "bidirectional"))
      (node (ref "PCIE-NORTH") (pin "A16") (pinfunction "LVDS_4A_A16") (pintype "passive"))
    )
    (net (code "56") (name "B15_L5_P") (class "Default")
      (node (ref "JM2") (pin "6") (pinfunction "6_6") (pintype "bidirectional"))
      (node (ref "PCIE-NORTH") (pin "A17") (pinfunction "LVDS_4B_A17") (pintype "passive"))
    )
    (net (code "57") (name "B15_L6_N") (class "Default")
      (node (ref "JM2") (pin "26") (pinfunction "26_26") (pintype "bidirectional"))
      (node (ref "PCIE-NORTH") (pin "A5") (pinfunction "LVDS_1A_A5") (pintype "passive"))
    )
    (net (code "58") (name "B15_L6_P") (class "Default")
      (node (ref "JM2") (pin "24") (pinfunction "24_24") (pintype "bidirectional"))
      (node (ref "PCIE-NORTH") (pin "A6") (pinfunction "LVDS_1B_A6") (pintype "passive"))
    )
    (net (code "59") (name "B15_L7_N") (class "Default")
      (node (ref "JM2") (pin "1") (pinfunction "1_1") (pintype "bidirectional"))
      (node (ref "PCIE-NORTH") (pin "B17") (pinfunction "LVDS_5B_B17") (pintype "passive"))
    )
    (net (code "60") (name "B15_L7_P") (class "Default")
      (node (ref "JM2") (pin "3") (pinfunction "3_3") (pintype "bidirectional"))
      (node (ref "PCIE-NORTH") (pin "B16") (pinfunction "LVDS_5A_B16") (pintype "passive"))
    )
    (net (code "61") (name "B15_L8_N") (class "Default")
      (node (ref "JM2") (pin "7") (pinfunction "7_7") (pintype "bidirectional"))
    )
    (net (code "62") (name "B15_L8_P") (class "Default")
      (node (ref "JM2") (pin "5") (pinfunction "5_5") (pintype "bidirectional"))
    )
    (net (code "63") (name "B15_L9_N") (class "Default")
      (node (ref "JM2") (pin "15") (pinfunction "15_15") (pintype "bidirectional"))
    )
    (net (code "64") (name "B15_L9_P") (class "Default")
      (node (ref "JM2") (pin "13") (pinfunction "13_13") (pintype "bidirectional"))
    )
    (net (code "65") (name "B15_L10_N") (class "Default")
      (node (ref "JM2") (pin "11") (pinfunction "11_11") (pintype "bidirectional"))
      (node (ref "PCIE-NORTH") (pin "A8") (pinfunction "LVDS_2A_A8") (pintype "passive"))
    )
    (net (code "66") (name "B15_L10_P") (class "Default")
      (node (ref "JM2") (pin "9") (pinfunction "9_9") (pintype "bidirectional"))
      (node (ref "PCIE-NORTH") (pin "A9") (pinfunction "LVDS_2B_A9") (pintype "passive"))
    )
    (net (code "67") (name "B15_L11_N") (class "Default")
      (node (ref "JM2") (pin "30") (pinfunction "30_30") (pintype "bidirectional"))
    )
    (net (code "68") (name "B15_L11_P") (class "Default")
      (node (ref "JM2") (pin "28") (pinfunction "28_28") (pintype "bidirectional"))
    )
    (net (code "69") (name "B15_L12_N") (class "Default")
      (node (ref "JM2") (pin "34") (pinfunction "34_34") (pintype "bidirectional"))
      (node (ref "PCIE-SOUTH") (pin "A8") (pinfunction "LVDS_2A_A8") (pintype "passive"))
    )
    (net (code "70") (name "B15_L12_P") (class "Default")
      (node (ref "JM2") (pin "32") (pinfunction "32_32") (pintype "bidirectional"))
      (node (ref "PCIE-SOUTH") (pin "A9") (pinfunction "LVDS_2B_A9") (pintype "passive"))
    )
    (net (code "71") (name "B15_L13_N") (class "Default")
      (node (ref "JM2") (pin "38") (pinfunction "38_38") (pintype "bidirectional"))
      (node (ref "PCIE-SOUTH") (pin "A6") (pinfunction "LVDS_1B_A6") (pintype "passive"))
    )
    (net (code "72") (name "B15_L13_P") (class "Default")
      (node (ref "JM2") (pin "40") (pinfunction "40_40") (pintype "bidirectional"))
      (node (ref "PCIE-SOUTH") (pin "A5") (pinfunction "LVDS_1A_A5") (pintype "passive"))
    )
    (net (code "73") (name "B15_L14_N") (class "Default")
      (node (ref "JM2") (pin "42") (pinfunction "42_42") (pintype "bidirectional"))
    )
    (net (code "74") (name "B15_L14_P") (class "Default")
      (node (ref "JM2") (pin "44") (pinfunction "44_44") (pintype "bidirectional"))
    )
    (net (code "75") (name "B15_L15_N") (class "Default")
      (node (ref "JM2") (pin "19") (pinfunction "19_19") (pintype "bidirectional"))
      (node (ref "PCIE-NORTH") (pin "A3") (pinfunction "LVDS_0B_A3") (pintype "passive"))
    )
    (net (code "76") (name "B15_L15_P") (class "Default")
      (node (ref "JM2") (pin "21") (pinfunction "21_21") (pintype "bidirectional"))
      (node (ref "PCIE-NORTH") (pin "A2") (pinfunction "LVDS_0A_A2") (pintype "passive"))
    )
    (net (code "77") (name "B15_L16_N") (class "Default")
      (node (ref "JM2") (pin "23") (pinfunction "23_23") (pintype "bidirectional"))
    )
    (net (code "78") (name "B15_L16_P") (class "Default")
      (node (ref "JM2") (pin "25") (pinfunction "25_25") (pintype "bidirectional"))
    )
    (net (code "79") (name "B15_L17_N") (class "Default")
      (node (ref "JM2") (pin "31") (pinfunction "31_31") (pintype "bidirectional"))
    )
    (net (code "80") (name "B15_L17_P") (class "Default")
      (node (ref "JM2") (pin "33") (pinfunction "33_33") (pintype "bidirectional"))
    )
    (net (code "81") (name "B15_L18_N") (class "Default")
      (node (ref "JM2") (pin "27") (pinfunction "27_27") (pintype "bidirectional"))
      (node (ref "PCIE-SOUTH") (pin "A17") (pinfunction "LVDS_4B_A17") (pintype "passive"))
    )
    (net (code "82") (name "B15_L18_P") (class "Default")
      (node (ref "JM2") (pin "29") (pinfunction "29_29") (pintype "bidirectional"))
      (node (ref "PCIE-SOUTH") (pin "A16") (pinfunction "LVDS_4A_A16") (pintype "passive"))
    )
    (net (code "83") (name "B15_L19_N") (class "Default")
      (node (ref "JM2") (pin "41") (pinfunction "41_41") (pintype "bidirectional"))
      (node (ref "PCIE-SOUTH") (pin "B17") (pinfunction "LVDS_5B_B17") (pintype "passive"))
    )
    (net (code "84") (name "B15_L19_P") (class "Default")
      (node (ref "JM2") (pin "43") (pinfunction "43_43") (pintype "bidirectional"))
      (node (ref "PCIE-SOUTH") (pin "B16") (pinfunction "LVDS_5A_B16") (pintype "passive"))
    )
    (net (code "85") (name "B15_L20_N") (class "Default")
      (node (ref "JM2") (pin "50") (pinfunction "50_50") (pintype "bidirectional"))
    )
    (net (code "86") (name "B15_L20_P") (class "Default")
      (node (ref "JM2") (pin "52") (pinfunction "52_52") (pintype "bidirectional"))
    )
    (net (code "87") (name "B15_L21_N") (class "Default")
      (node (ref "JM2") (pin "45") (pinfunction "45_45") (pintype "bidirectional"))
    )
    (net (code "88") (name "B15_L21_P") (class "Default")
      (node (ref "JM2") (pin "47") (pinfunction "47_47") (pintype "bidirectional"))
    )
    (net (code "89") (name "B15_L22_N") (class "Default")
      (node (ref "JM2") (pin "46") (pinfunction "46_46") (pintype "bidirectional"))
      (node (ref "PCIE-SOUTH") (pin "A3") (pinfunction "LVDS_0B_A3") (pintype "passive"))
    )
    (net (code "90") (name "B15_L22_P") (class "Default")
      (node (ref "JM2") (pin "48") (pinfunction "48_48") (pintype "bidirectional"))
      (node (ref "PCIE-SOUTH") (pin "A2") (pinfunction "LVDS_0A_A2") (pintype "passive"))
    )
    (net (code "91") (name "B15_L23_N") (class "Default")
      (node (ref "JM2") (pin "51") (pinfunction "51_51") (pintype "bidirectional"))
      (node (ref "PCIE-SOUTH") (pin "A13") (pinfunction "LVDS_3A_A13") (pintype "passive"))
    )
    (net (code "92") (name "B15_L23_P") (class "Default")
      (node (ref "JM2") (pin "49") (pinfunction "49_49") (pintype "bidirectional"))
      (node (ref "PCIE-SOUTH") (pin "A14") (pinfunction "LVDS_3B_A14") (pintype "passive"))
    )
    (net (code "93") (name "B15_L24_N") (class "Default")
      (node (ref "JM2") (pin "37") (pinfunction "37_37") (pintype "bidirectional"))
    )
    (net (code "94") (name "B15_L24_P") (class "Default")
      (node (ref "JM2") (pin "39") (pinfunction "39_39") (pintype "bidirectional"))
    )
    (net (code "95") (name "B34_L1_N") (class "Default")
      (node (ref "JM1") (pin "37") (pinfunction "37_37") (pintype "bidirectional"))
    )
    (net (code "96") (name "B34_L1_P") (class "Default")
      (node (ref "JM1") (pin "35") (pinfunction "35_35") (pintype "bidirectional"))
    )
    (net (code "97") (name "B34_L2_N") (class "Default")
      (node (ref "JM1") (pin "33") (pinfunction "33_33") (pintype "bidirectional"))
    )
    (net (code "98") (name "B34_L2_P") (class "Default")
      (node (ref "JM1") (pin "31") (pinfunction "31_31") (pintype "bidirectional"))
    )
    (net (code "99") (name "B34_L3_N") (class "Default")
      (node (ref "JM1") (pin "42") (pinfunction "42_42") (pintype "bidirectional"))
    )
    (net (code "100") (name "B34_L3_P") (class "Default")
      (node (ref "JM1") (pin "40") (pinfunction "40_40") (pintype "bidirectional"))
    )
    (net (code "101") (name "B34_L4_N") (class "Default")
      (node (ref "JM1") (pin "41") (pinfunction "41_41") (pintype "bidirectional"))
    )
    (net (code "102") (name "B34_L4_P") (class "Default")
      (node (ref "JM1") (pin "39") (pinfunction "39_39") (pintype "bidirectional"))
    )
    (net (code "103") (name "B34_L5_N") (class "Default")
      (node (ref "JM1") (pin "45") (pinfunction "45_45") (pintype "bidirectional"))
    )
    (net (code "104") (name "B34_L5_P") (class "Default")
      (node (ref "JM1") (pin "43") (pinfunction "43_43") (pintype "bidirectional"))
    )
    (net (code "105") (name "B34_L6_N") (class "Default")
      (node (ref "JM1") (pin "34") (pinfunction "34_34") (pintype "bidirectional"))
    )
    (net (code "106") (name "B34_L6_P") (class "Default")
      (node (ref "JM1") (pin "32") (pinfunction "32_32") (pintype "bidirectional"))
    )
    (net (code "107") (name "B34_L7_N") (class "Default")
      (node (ref "JM1") (pin "38") (pinfunction "38_38") (pintype "bidirectional"))
    )
    (net (code "108") (name "B34_L7_P") (class "Default")
      (node (ref "JM1") (pin "36") (pinfunction "36_36") (pintype "bidirectional"))
    )
    (net (code "109") (name "B34_L8_N") (class "Default")
      (node (ref "JM1") (pin "52") (pinfunction "52_52") (pintype "bidirectional"))
    )
    (net (code "110") (name "B34_L8_P") (class "Default")
      (node (ref "JM1") (pin "50") (pinfunction "50_50") (pintype "bidirectional"))
    )
    (net (code "111") (name "B34_L9_N") (class "Default")
      (node (ref "JM1") (pin "46") (pinfunction "46_46") (pintype "bidirectional"))
    )
    (net (code "112") (name "B34_L9_P") (class "Default")
      (node (ref "JM1") (pin "44") (pinfunction "44_44") (pintype "bidirectional"))
    )
    (net (code "113") (name "B34_L10_N") (class "Default")
      (node (ref "JM1") (pin "51") (pinfunction "51_51") (pintype "bidirectional"))
    )
    (net (code "114") (name "B34_L10_P") (class "Default")
      (node (ref "JM1") (pin "49") (pinfunction "49_49") (pintype "bidirectional"))
    )
    (net (code "115") (name "B34_L11_N") (class "Default")
      (node (ref "JM1") (pin "53") (pinfunction "53_53") (pintype "bidirectional"))
    )
    (net (code "116") (name "B34_L11_P") (class "Default")
      (node (ref "JM1") (pin "55") (pinfunction "55_55") (pintype "bidirectional"))
    )
    (net (code "117") (name "B34_L12_N") (class "Default")
      (node (ref "JM1") (pin "57") (pinfunction "57_57") (pintype "bidirectional"))
    )
    (net (code "118") (name "B34_L12_P") (class "Default")
      (node (ref "JM1") (pin "59") (pinfunction "59_59") (pintype "bidirectional"))
    )
    (net (code "119") (name "B34_L13_N") (class "Default")
      (node (ref "JM1") (pin "56") (pinfunction "56_56") (pintype "bidirectional"))
    )
    (net (code "120") (name "B34_L13_P") (class "Default")
      (node (ref "JM1") (pin "54") (pinfunction "54_54") (pintype "bidirectional"))
    )
    (net (code "121") (name "B34_L14_N") (class "Default")
      (node (ref "JM1") (pin "60") (pinfunction "60_60") (pintype "bidirectional"))
    )
    (net (code "122") (name "B34_L14_P") (class "Default")
      (node (ref "JM1") (pin "58") (pinfunction "58_58") (pintype "bidirectional"))
    )
    (net (code "123") (name "B34_L15_N") (class "Default")
      (node (ref "JM1") (pin "62") (pinfunction "62_62") (pintype "bidirectional"))
    )
    (net (code "124") (name "B34_L15_P") (class "Default")
      (node (ref "JM1") (pin "64") (pinfunction "64_64") (pintype "bidirectional"))
    )
    (net (code "125") (name "B34_L16_N") (class "Default")
      (node (ref "JM1") (pin "68") (pinfunction "68_68") (pintype "bidirectional"))
    )
    (net (code "126") (name "B34_L16_P") (class "Default")
      (node (ref "JM1") (pin "70") (pinfunction "70_70") (pintype "bidirectional"))
    )
    (net (code "127") (name "B34_L17_N") (class "Default")
      (node (ref "JM1") (pin "63") (pinfunction "63_63") (pintype "bidirectional"))
    )
    (net (code "128") (name "B34_L17_P") (class "Default")
      (node (ref "JM1") (pin "65") (pinfunction "65_65") (pintype "bidirectional"))
    )
    (net (code "129") (name "B34_L18_N") (class "Default")
      (node (ref "JM1") (pin "74") (pinfunction "74_74") (pintype "bidirectional"))
    )
    (net (code "130") (name "B34_L18_P") (class "Default")
      (node (ref "JM1") (pin "72") (pinfunction "72_72") (pintype "bidirectional"))
    )
    (net (code "131") (name "B34_L19_N") (class "Default")
      (node (ref "JM1") (pin "71") (pinfunction "71_71") (pintype "bidirectional"))
    )
    (net (code "132") (name "B34_L19_P") (class "Default")
      (node (ref "JM1") (pin "73") (pinfunction "73_73") (pintype "bidirectional"))
    )
    (net (code "133") (name "B34_L20_N") (class "Default")
      (node (ref "JM1") (pin "76") (pinfunction "76_76") (pintype "bidirectional"))
      (node (ref "R4") (pin "1") (pinfunction "1_1") (pintype "passive"))
    )
    (net (code "134") (name "B34_L20_P") (class "Default")
      (node (ref "JM1") (pin "78") (pinfunction "78_78") (pintype "bidirectional"))
      (node (ref "R5") (pin "1") (pinfunction "1_1") (pintype "passive"))
    )
    (net (code "135") (name "B34_L21_N") (class "Default")
      (node (ref "JM1") (pin "69") (pinfunction "69_69") (pintype "bidirectional"))
    )
    (net (code "136") (name "B34_L21_P") (class "Default")
      (node (ref "JM1") (pin "67") (pinfunction "67_67") (pintype "bidirectional"))
    )
    (net (code "137") (name "B34_L22_N") (class "Default")
      (node (ref "JM1") (pin "75") (pinfunction "75_75") (pintype "bidirectional"))
    )
    (net (code "138") (name "B34_L22_P") (class "Default")
      (node (ref "JM1") (pin "77") (pinfunction "77_77") (pintype "bidirectional"))
    )
    (net (code "139") (name "B34_L23_N") (class "Default")
      (node (ref "JM1") (pin "79") (pinfunction "79_79") (pintype "bidirectional"))
    )
    (net (code "140") (name "B34_L23_P") (class "Default")
      (node (ref "JM1") (pin "81") (pinfunction "81_81") (pintype "bidirectional"))
    )
    (net (code "141") (name "B34_L24_N") (class "Default")
      (node (ref "JM1") (pin "80") (pinfunction "80_80") (pintype "bidirectional"))
      (node (ref "R6") (pin "1") (pinfunction "1_1") (pintype "passive"))
    )
    (net (code "142") (name "B34_L24_P") (class "Default")
      (node (ref "JM1") (pin "82") (pinfunction "82_82") (pintype "bidirectional"))
      (node (ref "R7") (pin "1") (pinfunction "1_1") (pintype "passive"))
    )
    (net (code "143") (name "BOOTMODE") (class "Default")
      (node (ref "JM2") (pin "100") (pinfunction "100_100") (pintype "bidirectional"))
      (node (ref "JP3") (pin "1") (pinfunction "1_1") (pintype "passive"))
    )
    (net (code "144") (name "DONE") (class "Default")
      (node (ref "D5") (pin "A@1") (pinfunction "A_A@1") (pintype "passive"))
      (node (ref "JM1") (pin "96") (pinfunction "96_96") (pintype "bidirectional"))
      (node (ref "R3") (pin "1") (pinfunction "1_1") (pintype "passive"))
    )
    (net (code "145") (name "GND") (class "Default")
      (node (ref "C1") (pin "2") (pinfunction "2_2") (pintype "passive"))
      (node (ref "C10") (pin "2") (pinfunction "2_2") (pintype "passive"))
      (node (ref "C11") (pin "2") (pinfunction "2_2") (pintype "passive"))
      (node (ref "C12") (pin "2") (pinfunction "2_2") (pintype "passive"))
      (node (ref "C13") (pin "2") (pinfunction "2_2") (pintype "passive"))
      (node (ref "C14") (pin "2") (pinfunction "2_2") (pintype "passive"))
      (node (ref "C15") (pin "2") (pinfunction "2_2") (pintype "passive"))
      (node (ref "C16") (pin "2") (pinfunction "2_2") (pintype "passive"))
      (node (ref "C22") (pin "2") (pinfunction "2_2") (pintype "passive"))
      (node (ref "C23") (pin "2") (pinfunction "2_2") (pintype "passive"))
      (node (ref "C24") (pin "2") (pinfunction "2_2") (pintype "passive"))
      (node (ref "C25") (pin "2") (pinfunction "2_2") (pintype "passive"))
      (node (ref "C26") (pin "2") (pinfunction "2_2") (pintype "passive"))
      (node (ref "C27") (pin "2") (pinfunction "2_2") (pintype "passive"))
      (node (ref "C28") (pin "2") (pinfunction "2_2") (pintype "passive"))
      (node (ref "C29") (pin "2") (pinfunction "2_2") (pintype "passive"))
      (node (ref "C30") (pin "2") (pinfunction "2_2") (pintype "passive"))
      (node (ref "C31") (pin "2") (pinfunction "2_2") (pintype "passive"))
      (node (ref "C32") (pin "2") (pinfunction "2_2") (pintype "passive"))
      (node (ref "C33") (pin "2") (pinfunction "2_2") (pintype "passive"))
      (node (ref "C34") (pin "2") (pinfunction "2_2") (pintype "passive"))
      (node (ref "C40") (pin "2") (pinfunction "2_2") (pintype "passive"))
      (node (ref "C41") (pin "2") (pinfunction "2_2") (pintype "passive"))
      (node (ref "C42") (pin "2") (pinfunction "2_2") (pintype "passive"))
      (node (ref "C43") (pin "2") (pinfunction "2_2") (pintype "passive"))
      (node (ref "C44") (pin "2") (pinfunction "2_2") (pintype "passive"))
      (node (ref "C45") (pin "2") (pinfunction "2_2") (pintype "passive"))
      (node (ref "C46") (pin "2") (pinfunction "2_2") (pintype "passive"))
      (node (ref "C47") (pin "2") (pinfunction "2_2") (pintype "passive"))
      (node (ref "C48") (pin "2") (pinfunction "2_2") (pintype "passive"))
      (node (ref "C49") (pin "2") (pinfunction "2_2") (pintype "passive"))
      (node (ref "C5") (pin "2") (pinfunction "2_2") (pintype "passive"))
      (node (ref "C50") (pin "2") (pinfunction "2_2") (pintype "passive"))
      (node (ref "C51") (pin "2") (pinfunction "2_2") (pintype "passive"))
      (node (ref "C52") (pin "2") (pinfunction "2_2") (pintype "passive"))
      (node (ref "C53") (pin "2") (pinfunction "2_2") (pintype "passive"))
      (node (ref "C6") (pin "2") (pinfunction "2_2") (pintype "passive"))
      (node (ref "C7") (pin "2") (pinfunction "2_2") (pintype "passive"))
      (node (ref "C8") (pin "2") (pinfunction "2_2") (pintype "passive"))
      (node (ref "C9") (pin "2") (pinfunction "2_2") (pintype "passive"))
      (node (ref "D5") (pin "C@1") (pinfunction "C_C@1") (pintype "passive"))
      (node (ref "JM1") (pin "100") (pinfunction "100_100") (pintype "bidirectional"))
      (node (ref "JM1") (pin "11") (pinfunction "11_11") (pintype "bidirectional"))
      (node (ref "JM1") (pin "12") (pinfunction "12_12") (pintype "bidirectional"))
      (node (ref "JM1") (pin "17") (pinfunction "17_17") (pintype "bidirectional"))
      (node (ref "JM1") (pin "18") (pinfunction "18_18") (pintype "bidirectional"))
      (node (ref "JM1") (pin "23") (pinfunction "23_23") (pintype "bidirectional"))
      (node (ref "JM1") (pin "24") (pinfunction "24_24") (pintype "bidirectional"))
      (node (ref "JM1") (pin "29") (pinfunction "29_29") (pintype "bidirectional"))
      (node (ref "JM1") (pin "30") (pinfunction "30_30") (pintype "bidirectional"))
      (node (ref "JM1") (pin "47") (pinfunction "47_47") (pintype "bidirectional"))
      (node (ref "JM1") (pin "48") (pinfunction "48_48") (pintype "bidirectional"))
      (node (ref "JM1") (pin "5") (pinfunction "5_5") (pintype "bidirectional"))
      (node (ref "JM1") (pin "6") (pinfunction "6_6") (pintype "bidirectional"))
      (node (ref "JM1") (pin "66") (pinfunction "66_66") (pintype "bidirectional"))
      (node (ref "JM1") (pin "84") (pinfunction "84_84") (pintype "bidirectional"))
      (node (ref "JM1") (pin "98") (pinfunction "98_98") (pintype "bidirectional"))
      (node (ref "JM1") (pin "F1") (pinfunction "F1_F1") (pintype "bidirectional"))
      (node (ref "JM1") (pin "F2") (pinfunction "F2_F2") (pintype "bidirectional"))
      (node (ref "JM2") (pin "17") (pinfunction "17_17") (pintype "bidirectional"))
      (node (ref "JM2") (pin "35") (pinfunction "35_35") (pintype "bidirectional"))
      (node (ref "JM2") (pin "36") (pinfunction "36_36") (pintype "bidirectional"))
      (node (ref "JM2") (pin "72") (pinfunction "72_72") (pintype "bidirectional"))
      (node (ref "JM2") (pin "83") (pinfunction "83_83") (pintype "bidirectional"))
      (node (ref "JM2") (pin "90") (pinfunction "90_90") (pintype "bidirectional"))
      (node (ref "JM2") (pin "F1") (pinfunction "F1_F1") (pintype "bidirectional"))
      (node (ref "JM2") (pin "F2") (pinfunction "F2_F2") (pintype "bidirectional"))
      (node (ref "JP2") (pin "1") (pinfunction "1_1") (pintype "passive"))
      (node (ref "JP3") (pin "2") (pinfunction "2_2") (pintype "passive"))
      (node (ref "PCIE-NORTH") (pin "A1") (pinfunction "GND_A1") (pintype "passive"))
      (node (ref "PCIE-NORTH") (pin "A10") (pinfunction "GND_A10") (pintype "passive"))
      (node (ref "PCIE-NORTH") (pin "A12") (pinfunction "GND_A12") (pintype "passive"))
      (node (ref "PCIE-NORTH") (pin "A15") (pinfunction "GND_A15") (pintype "passive"))
      (node (ref "PCIE-NORTH") (pin "A18") (pinfunction "GND_A18") (pintype "passive"))
      (node (ref "PCIE-NORTH") (pin "A4") (pinfunction "GND_A4") (pintype "passive"))
      (node (ref "PCIE-NORTH") (pin "A7") (pinfunction "GND_A7") (pintype "passive"))
      (node (ref "PCIE-NORTH") (pin "B15") (pinfunction "GND_B15") (pintype "passive"))
      (node (ref "PCIE-NORTH") (pin "B18") (pinfunction "GND_B18") (pintype "passive"))
      (node (ref "PCIE-SOUTH") (pin "A1") (pinfunction "GND_A1") (pintype "passive"))
      (node (ref "PCIE-SOUTH") (pin "A10") (pinfunction "GND_A10") (pintype "passive"))
      (node (ref "PCIE-SOUTH") (pin "A12") (pinfunction "GND_A12") (pintype "passive"))
      (node (ref "PCIE-SOUTH") (pin "A15") (pinfunction "GND_A15") (pintype "passive"))
      (node (ref "PCIE-SOUTH") (pin "A18") (pinfunction "GND_A18") (pintype "passive"))
      (node (ref "PCIE-SOUTH") (pin "A4") (pinfunction "GND_A4") (pintype "passive"))
      (node (ref "PCIE-SOUTH") (pin "A7") (pinfunction "GND_A7") (pintype "passive"))
      (node (ref "PCIE-SOUTH") (pin "B15") (pinfunction "GND_B15") (pintype "passive"))
      (node (ref "PCIE-SOUTH") (pin "B18") (pinfunction "GND_B18") (pintype "passive"))
      (node (ref "R10") (pin "2") (pinfunction "2_2") (pintype "passive"))
      (node (ref "R11") (pin "2") (pinfunction "2_2") (pintype "passive"))
      (node (ref "R12") (pin "2") (pinfunction "2_2") (pintype "passive"))
      (node (ref "R13") (pin "2") (pinfunction "2_2") (pintype "passive"))
      (node (ref "R14") (pin "2") (pinfunction "2_2") (pintype "passive"))
      (node (ref "R2") (pin "2") (pinfunction "2_2") (pintype "passive"))
      (node (ref "R8") (pin "2") (pinfunction "2_2") (pintype "passive"))
      (node (ref "R9") (pin "2") (pinfunction "2_2") (pintype "passive"))
      (node (ref "U1") (pin "1") (pinfunction "A0_1") (pintype "input"))
      (node (ref "U1") (pin "2") (pinfunction "A1_2") (pintype "input"))
      (node (ref "U1") (pin "3") (pinfunction "A2_3") (pintype "input"))
      (node (ref "U1") (pin "4") (pinfunction "GND_4") (pintype "passive"))
      (node (ref "U1") (pin "EP") (pinfunction "EP_EP") (pintype "passive"))
      (node (ref "U2") (pin "1") (pinfunction "VEE_SDI_1") (pintype "power_in"))
      (node (ref "U2") (pin "14") (pinfunction "VSS_14") (pintype "power_in"))
      (node (ref "U2") (pin "15") (pinfunction "VSS_15") (pintype "power_in"))
      (node (ref "U2") (pin "19") (pinfunction "VEE_CORE_19") (pintype "power_in"))
      (node (ref "U2") (pin "21") (pinfunction "VEEO_21") (pintype "power_in"))
      (node (ref "U2") (pin "28") (pinfunction "VEEO_28") (pintype "power_in"))
      (node (ref "U2") (pin "31") (pinfunction "VEE_CORE_31") (pintype "power_in"))
      (node (ref "U2") (pin "37") (pinfunction "VEE_CORE_37") (pintype "power_in"))
      (node (ref "U2") (pin "38") (pinfunction "VEE_CORE_38") (pintype "power_in"))
      (node (ref "U2") (pin "8") (pinfunction "VEE_SDI_8") (pintype "power_in"))
      (node (ref "U3") (pin "1") (pinfunction "VEE_DDI_1") (pintype "power_in"))
      (node (ref "U3") (pin "14") (pinfunction "VSS_14") (pintype "power_in"))
      (node (ref "U3") (pin "15") (pinfunction "VSS_15") (pintype "power_in"))
      (node (ref "U3") (pin "19") (pinfunction "VEE_CORE_19") (pintype "power_in"))
      (node (ref "U3") (pin "21") (pinfunction "VEEO_21") (pintype "power_in"))
      (node (ref "U3") (pin "28") (pinfunction "VEEO_28") (pintype "power_in"))
      (node (ref "U3") (pin "31") (pinfunction "VEE_CORE_31") (pintype "power_in"))
      (node (ref "U3") (pin "37") (pinfunction "VEE_CORE_37") (pintype "power_in"))
      (node (ref "U3") (pin "38") (pinfunction "VEE_CORE_38") (pintype "power_in"))
      (node (ref "U3") (pin "8") (pinfunction "VEE_DDI_8") (pintype "power_in"))
      (node (ref "U4") (pin "1") (pinfunction "VEE_DDI_1") (pintype "power_in"))
      (node (ref "U4") (pin "14") (pinfunction "VSS_14") (pintype "power_in"))
      (node (ref "U4") (pin "15") (pinfunction "VSS_15") (pintype "power_in"))
      (node (ref "U4") (pin "19") (pinfunction "VEE_CORE_19") (pintype "power_in"))
      (node (ref "U4") (pin "21") (pinfunction "VEEO_21") (pintype "power_in"))
      (node (ref "U4") (pin "28") (pinfunction "VEEO_28") (pintype "power_in"))
      (node (ref "U4") (pin "31") (pinfunction "VEE_CORE_31") (pintype "power_in"))
      (node (ref "U4") (pin "37") (pinfunction "VEE_CORE_37") (pintype "power_in"))
      (node (ref "U4") (pin "38") (pinfunction "VEE_CORE_38") (pintype "power_in"))
      (node (ref "U4") (pin "8") (pinfunction "VEE_DDI_8") (pintype "power_in"))
      (node (ref "U5") (pin "3") (pinfunction "GND_3") (pintype "passive"))
      (node (ref "X1") (pin "2@1") (pinfunction "GND_2@1") (pintype "passive"))
      (node (ref "X1") (pin "2@2") (pinfunction "GND_2@2") (pintype "passive"))
      (node (ref "X1") (pin "2@3") (pinfunction "GND_2@3") (pintype "passive"))
      (node (ref "X2") (pin "2@1") (pinfunction "GND_2@1") (pintype "passive"))
      (node (ref "X2") (pin "2@2") (pinfunction "GND_2@2") (pintype "passive"))
      (node (ref "X2") (pin "2@3") (pinfunction "GND_2@3") (pintype "passive"))
      (node (ref "X3") (pin "2@1") (pinfunction "GND_2@1") (pintype "passive"))
      (node (ref "X3") (pin "2@2") (pinfunction "GND_2@2") (pintype "passive"))
      (node (ref "X3") (pin "2@3") (pinfunction "GND_2@3") (pintype "passive"))
    )
    (net (code "146") (name "I2C_V") (class "Default")
      (node (ref "C1") (pin "1") (pinfunction "1_1") (pintype "passive"))
      (node (ref "PCIE-NORTH") (pin "B3") (pinfunction "V_I2C_B3") (pintype "passive"))
      (node (ref "R1") (pin "1") (pinfunction "1_1") (pintype "passive"))
      (node (ref "U1") (pin "8") (pinfunction "VCC_8") (pintype "power_in"))
    )
    (net (code "147") (name "MGT_CLK0_N") (class "Default")
      (node (ref "C55") (pin "2") (pinfunction "2_2") (pintype "passive"))
      (node (ref "JM1") (pin "4") (pinfunction "4_4") (pintype "bidirectional"))
    )
    (net (code "148") (name "MGT_CLK0_P") (class "Default")
      (node (ref "C54") (pin "2") (pinfunction "2_2") (pintype "passive"))
      (node (ref "JM1") (pin "2") (pinfunction "2_2") (pintype "bidirectional"))
    )
    (net (code "149") (name "MGT_RX0_N") (class "Default")
      (node (ref "JM1") (pin "21") (pinfunction "21_21") (pintype "bidirectional"))
      (node (ref "U2") (pin "27") (pinfunction "DDO0_27") (pintype "output"))
    )
    (net (code "150") (name "MGT_RX0_P") (class "Default")
      (node (ref "JM1") (pin "19") (pinfunction "19_19") (pintype "bidirectional"))
      (node (ref "U2") (pin "26") (pinfunction "~{DDO0}_26") (pintype "output"))
    )
    (net (code "151") (name "MGT_RX1_N") (class "Default")
      (node (ref "JM1") (pin "15") (pinfunction "15_15") (pintype "bidirectional"))
      (node (ref "U2") (pin "23") (pinfunction "DDO1/RCO_23") (pintype "output"))
    )
    (net (code "152") (name "MGT_RX1_P") (class "Default")
      (node (ref "JM1") (pin "13") (pinfunction "13_13") (pintype "bidirectional"))
      (node (ref "U2") (pin "22") (pinfunction "~{DDO1}/~{RCO}_22") (pintype "output"))
    )
    (net (code "153") (name "MGT_RX2_N") (class "Default")
      (node (ref "JM1") (pin "9") (pinfunction "9_9") (pintype "bidirectional"))
    )
    (net (code "154") (name "MGT_RX2_P") (class "Default")
      (node (ref "JM1") (pin "7") (pinfunction "7_7") (pintype "bidirectional"))
    )
    (net (code "155") (name "MGT_RX3_N") (class "Default")
      (node (ref "JM1") (pin "3") (pinfunction "3_3") (pintype "bidirectional"))
    )
    (net (code "156") (name "MGT_RX3_P") (class "Default")
      (node (ref "JM1") (pin "1") (pinfunction "1_1") (pintype "bidirectional"))
    )
    (net (code "157") (name "MGT_TX0_N") (class "Default")
      (node (ref "JM1") (pin "28") (pinfunction "28_28") (pintype "bidirectional"))
      (node (ref "U4") (pin "6") (pinfunction "DDI_6") (pintype "input"))
    )
    (net (code "158") (name "MGT_TX0_P") (class "Default")
      (node (ref "JM1") (pin "26") (pinfunction "26_26") (pintype "bidirectional"))
      (node (ref "U4") (pin "7") (pinfunction "~{DDI}_7") (pintype "input"))
    )
    (net (code "159") (name "MGT_TX1_N") (class "Default")
      (node (ref "JM1") (pin "22") (pinfunction "22_22") (pintype "bidirectional"))
      (node (ref "U3") (pin "6") (pinfunction "DDI_6") (pintype "input"))
    )
    (net (code "160") (name "MGT_TX1_P") (class "Default")
      (node (ref "JM1") (pin "20") (pinfunction "20_20") (pintype "bidirectional"))
      (node (ref "U3") (pin "7") (pinfunction "~{DDI}_7") (pintype "input"))
    )
    (net (code "161") (name "MGT_TX2_N") (class "Default")
      (node (ref "JM1") (pin "16") (pinfunction "16_16") (pintype "bidirectional"))
    )
    (net (code "162") (name "MGT_TX2_P") (class "Default")
      (node (ref "JM1") (pin "14") (pinfunction "14_14") (pintype "bidirectional"))
    )
    (net (code "163") (name "MGT_TX3_N") (class "Default")
      (node (ref "JM1") (pin "10") (pinfunction "10_10") (pintype "bidirectional"))
    )
    (net (code "164") (name "MGT_TX3_P") (class "Default")
      (node (ref "JM1") (pin "8") (pinfunction "8_8") (pintype "bidirectional"))
    )
    (net (code "165") (name "N$26") (class "Default")
      (node (ref "U3") (pin "17") (pinfunction "GPIO0_17") (pintype "bidirectional"))
    )
    (net (code "166") (name "N$27") (class "Default")
      (node (ref "U3") (pin "18") (pinfunction "GPIO1_18") (pintype "bidirectional"))
    )
    (net (code "167") (name "N$28") (class "Default")
      (node (ref "U3") (pin "33") (pinfunction "GPIO2_33") (pintype "bidirectional"))
    )
    (net (code "168") (name "N$29") (class "Default")
      (node (ref "U3") (pin "36") (pinfunction "GPIO3_36") (pintype "bidirectional"))
    )
    (net (code "169") (name "N$30") (class "Default")
      (node (ref "U3") (pin "12") (pinfunction "SDOUT_12") (pintype "output"))
    )
    (net (code "170") (name "N$31") (class "Default")
      (node (ref "U3") (pin "11") (pinfunction "SDIN_11") (pintype "input"))
    )
    (net (code "171") (name "N$32") (class "Default")
      (node (ref "U3") (pin "13") (pinfunction "SCLK_13") (pintype "input"))
    )
    (net (code "172") (name "N$33") (class "Default")
      (node (ref "U3") (pin "10") (pinfunction "~{CS}_10") (pintype "input"))
    )
    (net (code "173") (name "N$34") (class "Default")
      (node (ref "U3") (pin "32") (pinfunction "RCLK_32") (pintype "input"))
    )
    (net (code "174") (name "N$39") (class "Default")
      (node (ref "U2") (pin "10") (pinfunction "~{CS}_10") (pintype "input"))
    )
    (net (code "175") (name "N$40") (class "Default")
      (node (ref "U2") (pin "13") (pinfunction "SCLK_13") (pintype "input"))
    )
    (net (code "176") (name "N$41") (class "Default")
      (node (ref "U2") (pin "11") (pinfunction "SDIN_11") (pintype "input"))
    )
    (net (code "177") (name "N$42") (class "Default")
      (node (ref "U2") (pin "12") (pinfunction "SDOUT_12") (pintype "output"))
    )
    (net (code "178") (name "N$43") (class "Default")
      (node (ref "U2") (pin "17") (pinfunction "GPIO0_17") (pintype "bidirectional"))
    )
    (net (code "179") (name "N$44") (class "Default")
      (node (ref "U2") (pin "18") (pinfunction "GPIO1_18") (pintype "bidirectional"))
    )
    (net (code "180") (name "N$45") (class "Default")
      (node (ref "U2") (pin "33") (pinfunction "GPIO2_33") (pintype "bidirectional"))
    )
    (net (code "181") (name "N$46") (class "Default")
      (node (ref "U2") (pin "36") (pinfunction "GPIO3_36") (pintype "bidirectional"))
    )
    (net (code "182") (name "N$81") (class "Default")
      (node (ref "U4") (pin "32") (pinfunction "RCLK_32") (pintype "input"))
    )
    (net (code "183") (name "N$82") (class "Default")
      (node (ref "U4") (pin "10") (pinfunction "~{CS}_10") (pintype "input"))
    )
    (net (code "184") (name "N$83") (class "Default")
      (node (ref "U4") (pin "13") (pinfunction "SCLK_13") (pintype "input"))
    )
    (net (code "185") (name "N$84") (class "Default")
      (node (ref "U4") (pin "11") (pinfunction "SDIN_11") (pintype "input"))
    )
    (net (code "186") (name "N$85") (class "Default")
      (node (ref "U4") (pin "12") (pinfunction "SDOUT_12") (pintype "output"))
    )
    (net (code "187") (name "N$86") (class "Default")
      (node (ref "U4") (pin "36") (pinfunction "GPIO3_36") (pintype "bidirectional"))
    )
    (net (code "188") (name "N$87") (class "Default")
      (node (ref "U4") (pin "33") (pinfunction "GPIO2_33") (pintype "bidirectional"))
    )
    (net (code "189") (name "N$88") (class "Default")
      (node (ref "U4") (pin "18") (pinfunction "GPIO1_18") (pintype "bidirectional"))
    )
    (net (code "190") (name "N$89") (class "Default")
      (node (ref "U4") (pin "17") (pinfunction "GPIO0_17") (pintype "bidirectional"))
    )
    (net (code "191") (name "N_5V") (class "Default")
      (node (ref "PCIE-NORTH") (pin "B12") (pinfunction "5V_B12") (pintype "passive"))
    )
    (net (code "192") (name "N_IO0") (class "Default")
      (node (ref "PCIE-NORTH") (pin "B4") (pinfunction "IO0_B4") (pintype "passive"))
    )
    (net (code "193") (name "N_IO1") (class "Default")
      (node (ref "PCIE-NORTH") (pin "B5") (pinfunction "IO1_B5") (pintype "passive"))
    )
    (net (code "194") (name "N_IO2") (class "Default")
      (node (ref "PCIE-NORTH") (pin "B6") (pinfunction "IO2_B6") (pintype "passive"))
    )
    (net (code "195") (name "N_IO3") (class "Default")
      (node (ref "PCIE-NORTH") (pin "B7") (pinfunction "IO3_B7") (pintype "passive"))
    )
    (net (code "196") (name "N_IO4") (class "Default")
      (node (ref "PCIE-NORTH") (pin "B8") (pinfunction "IO4_B8") (pintype "passive"))
    )
    (net (code "197") (name "N_IO5") (class "Default")
      (node (ref "PCIE-NORTH") (pin "B9") (pinfunction "IO5_B9") (pintype "passive"))
    )
    (net (code "198") (name "N_IO6") (class "Default")
      (node (ref "PCIE-NORTH") (pin "B10") (pinfunction "IO6_B10") (pintype "passive"))
    )
    (net (code "199") (name "N_IO7") (class "Default")
      (node (ref "PCIE-NORTH") (pin "B11") (pinfunction "IO7_B11") (pintype "passive"))
    )
    (net (code "200") (name "N_PCIE_V") (class "Default")
      (node (ref "PCIE-NORTH") (pin "B13") (pinfunction "VCC_B13") (pintype "passive"))
    )
    (net (code "201") (name "N_VCCIO") (class "Default")
      (node (ref "PCIE-NORTH") (pin "B14") (pinfunction "VCCIO_B14") (pintype "passive"))
    )
    (net (code "202") (name "Net-(C2-Pad1)") (class "Default")
      (node (ref "C2") (pin "1") (pinfunction "1_1") (pintype "passive"))
      (node (ref "X1") (pin "1") (pinfunction "1_1") (pintype "passive"))
    )
    (net (code "203") (name "Net-(C4-Pad2)") (class "Default")
      (node (ref "C4") (pin "2") (pinfunction "2_2") (pintype "passive"))
      (node (ref "R8") (pin "1") (pinfunction "1_1") (pintype "passive"))
    )
    (net (code "204") (name "Net-(C17-Pad2)") (class "Default")
      (node (ref "C17") (pin "2") (pinfunction "2_2") (pintype "passive"))
      (node (ref "X2") (pin "1") (pinfunction "1_1") (pintype "passive"))
    )
    (net (code "205") (name "Net-(C18-Pad2)") (class "Default")
      (node (ref "C18") (pin "2") (pinfunction "2_2") (pintype "passive"))
      (node (ref "R9") (pin "1") (pinfunction "1_1") (pintype "passive"))
    )
    (net (code "206") (name "Net-(C19-Pad2)") (class "Default")
      (node (ref "C19") (pin "2") (pinfunction "2_2") (pintype "passive"))
      (node (ref "R10") (pin "1") (pinfunction "1_1") (pintype "passive"))
    )
    (net (code "207") (name "Net-(C20-Pad2)") (class "Default")
      (node (ref "C20") (pin "2") (pinfunction "2_2") (pintype "passive"))
      (node (ref "R11") (pin "1") (pinfunction "1_1") (pintype "passive"))
    )
    (net (code "208") (name "Net-(C35-Pad2)") (class "Default")
      (node (ref "C35") (pin "2") (pinfunction "2_2") (pintype "passive"))
      (node (ref "X3") (pin "1") (pinfunction "1_1") (pintype "passive"))
    )
    (net (code "209") (name "Net-(C36-Pad2)") (class "Default")
      (node (ref "C36") (pin "2") (pinfunction "2_2") (pintype "passive"))
      (node (ref "R12") (pin "1") (pinfunction "1_1") (pintype "passive"))
    )
    (net (code "210") (name "Net-(C37-Pad2)") (class "Default")
      (node (ref "C37") (pin "2") (pinfunction "2_2") (pintype "passive"))
      (node (ref "R13") (pin "1") (pinfunction "1_1") (pintype "passive"))
    )
    (net (code "211") (name "Net-(C38-Pad2)") (class "Default")
      (node (ref "C38") (pin "2") (pinfunction "2_2") (pintype "passive"))
      (node (ref "R14") (pin "1") (pinfunction "1_1") (pintype "passive"))
    )
    (net (code "212") (name "Net-(D1-C)") (class "Default")
      (node (ref "D1") (pin "C@1") (pinfunction "C_C@1") (pintype "passive"))
      (node (ref "R4") (pin "2") (pinfunction "2_2") (pintype "passive"))
    )
    (net (code "213") (name "Net-(D2-C)") (class "Default")
      (node (ref "D2") (pin "C@1") (pinfunction "C_C@1") (pintype "passive"))
      (node (ref "R5") (pin "2") (pinfunction "2_2") (pintype "passive"))
    )
    (net (code "214") (name "Net-(D3-C)") (class "Default")
      (node (ref "D3") (pin "C@1") (pinfunction "C_C@1") (pintype "passive"))
      (node (ref "R6") (pin "2") (pinfunction "2_2") (pintype "passive"))
    )
    (net (code "215") (name "Net-(D4-C)") (class "Default")
      (node (ref "D4") (pin "C@1") (pinfunction "C_C@1") (pintype "passive"))
      (node (ref "R7") (pin "2") (pinfunction "2_2") (pintype "passive"))
    )
    (net (code "216") (name "Net-(U1-WP)") (class "Default")
      (node (ref "R1") (pin "2") (pinfunction "2_2") (pintype "passive"))
      (node (ref "R2") (pin "1") (pinfunction "1_1") (pintype "passive"))
      (node (ref "U1") (pin "7") (pinfunction "WP_7") (pintype "input"))
    )
    (net (code "217") (name "Net-(U2-LF+)") (class "Default")
      (node (ref "C3") (pin "1") (pinfunction "1_1") (pintype "passive"))
      (node (ref "U2") (pin "39") (pinfunction "LF+_39") (pintype "passive"))
    )
    (net (code "218") (name "Net-(U2-LF-)") (class "Default")
      (node (ref "C3") (pin "2") (pinfunction "2_2") (pintype "passive"))
      (node (ref "U2") (pin "40") (pinfunction "LF-_40") (pintype "passive"))
    )
    (net (code "219") (name "Net-(U2-SDI)") (class "Default")
      (node (ref "C2") (pin "2") (pinfunction "2_2") (pintype "passive"))
      (node (ref "U2") (pin "2") (pinfunction "SDI_2") (pintype "input"))
    )
    (net (code "220") (name "Net-(U2-SDI_TERM)") (class "Default")
      (node (ref "C4") (pin "1") (pinfunction "1_1") (pintype "passive"))
      (node (ref "U2") (pin "3") (pinfunction "SDI_TERM_3") (pintype "passive"))
    )
    (net (code "221") (name "Net-(U2-VCO_FILT)") (class "Default")
      (node (ref "C5") (pin "1") (pinfunction "1_1") (pintype "passive"))
      (node (ref "U2") (pin "34") (pinfunction "VCO_FILT_34") (pintype "passive"))
    )
    (net (code "222") (name "Net-(U2-VCO_FILT10)") (class "Default")
      (node (ref "C6") (pin "1") (pinfunction "1_1") (pintype "passive"))
      (node (ref "U2") (pin "30") (pinfunction "VCO_FILT10_30") (pintype "passive"))
    )
    (net (code "223") (name "Net-(U3-LF+)") (class "Default")
      (node (ref "C21") (pin "1") (pinfunction "1_1") (pintype "passive"))
      (node (ref "U3") (pin "39") (pinfunction "LF+_39") (pintype "passive"))
    )
    (net (code "224") (name "Net-(U3-LF-)") (class "Default")
      (node (ref "C21") (pin "2") (pinfunction "2_2") (pintype "passive"))
      (node (ref "U3") (pin "40") (pinfunction "LF-_40") (pintype "passive"))
    )
    (net (code "225") (name "Net-(U3-SDO0)") (class "Default")
      (node (ref "C17") (pin "1") (pinfunction "1_1") (pintype "passive"))
      (node (ref "U3") (pin "27") (pinfunction "SDO0_27") (pintype "output"))
    )
    (net (code "226") (name "Net-(U3-SDO1{slash}RCO)") (class "Default")
      (node (ref "C19") (pin "1") (pinfunction "1_1") (pintype "passive"))
      (node (ref "U3") (pin "23") (pinfunction "SDO1/RCO_23") (pintype "output"))
    )
    (net (code "227") (name "Net-(U3-TERM)") (class "Default")
      (node (ref "C22") (pin "1") (pinfunction "1_1") (pintype "passive"))
      (node (ref "U3") (pin "5") (pinfunction "TERM_5") (pintype "passive"))
    )
    (net (code "228") (name "Net-(U3-VCO_FILT)") (class "Default")
      (node (ref "C23") (pin "1") (pinfunction "1_1") (pintype "passive"))
      (node (ref "U3") (pin "34") (pinfunction "VCO_FILT_34") (pintype "passive"))
    )
    (net (code "229") (name "Net-(U3-VCO_FILT10)") (class "Default")
      (node (ref "C24") (pin "1") (pinfunction "1_1") (pintype "passive"))
      (node (ref "U3") (pin "30") (pinfunction "VCO_FILT10_30") (pintype "passive"))
    )
    (net (code "230") (name "Net-(U3-~{SDO0})") (class "Default")
      (node (ref "C20") (pin "1") (pinfunction "1_1") (pintype "passive"))
      (node (ref "U3") (pin "26") (pinfunction "~{SDO0}_26") (pintype "output"))
    )
    (net (code "231") (name "Net-(U3-~{SDO1}{slash}~{RCO})") (class "Default")
      (node (ref "C18") (pin "1") (pinfunction "1_1") (pintype "passive"))
      (node (ref "U3") (pin "22") (pinfunction "~{SDO1}/~{RCO}_22") (pintype "output"))
    )
    (net (code "232") (name "Net-(U4-LF+)") (class "Default")
      (node (ref "C39") (pin "1") (pinfunction "1_1") (pintype "passive"))
      (node (ref "U4") (pin "39") (pinfunction "LF+_39") (pintype "passive"))
    )
    (net (code "233") (name "Net-(U4-LF-)") (class "Default")
      (node (ref "C39") (pin "2") (pinfunction "2_2") (pintype "passive"))
      (node (ref "U4") (pin "40") (pinfunction "LF-_40") (pintype "passive"))
    )
    (net (code "234") (name "Net-(U4-SDO0)") (class "Default")
      (node (ref "C35") (pin "1") (pinfunction "1_1") (pintype "passive"))
      (node (ref "U4") (pin "27") (pinfunction "SDO0_27") (pintype "output"))
    )
    (net (code "235") (name "Net-(U4-SDO1{slash}RCO)") (class "Default")
      (node (ref "C37") (pin "1") (pinfunction "1_1") (pintype "passive"))
      (node (ref "U4") (pin "23") (pinfunction "SDO1/RCO_23") (pintype "output"))
    )
    (net (code "236") (name "Net-(U4-TERM)") (class "Default")
      (node (ref "C40") (pin "1") (pinfunction "1_1") (pintype "passive"))
      (node (ref "U4") (pin "5") (pinfunction "TERM_5") (pintype "passive"))
    )
    (net (code "237") (name "Net-(U4-VCO_FILT)") (class "Default")
      (node (ref "C41") (pin "1") (pinfunction "1_1") (pintype "passive"))
      (node (ref "U4") (pin "34") (pinfunction "VCO_FILT_34") (pintype "passive"))
    )
    (net (code "238") (name "Net-(U4-VCO_FILT10)") (class "Default")
      (node (ref "C42") (pin "1") (pinfunction "1_1") (pintype "passive"))
      (node (ref "U4") (pin "30") (pinfunction "VCO_FILT10_30") (pintype "passive"))
    )
    (net (code "239") (name "Net-(U4-~{SDO0})") (class "Default")
      (node (ref "C38") (pin "1") (pinfunction "1_1") (pintype "passive"))
      (node (ref "U4") (pin "26") (pinfunction "~{SDO0}_26") (pintype "output"))
    )
    (net (code "240") (name "Net-(U4-~{SDO1}{slash}~{RCO})") (class "Default")
      (node (ref "C36") (pin "1") (pinfunction "1_1") (pintype "passive"))
      (node (ref "U4") (pin "22") (pinfunction "~{SDO1}/~{RCO}_22") (pintype "output"))
    )
    (net (code "241") (name "Net-(U5-OUT+)") (class "Default")
      (node (ref "C54") (pin "1") (pinfunction "1_1") (pintype "passive"))
      (node (ref "R15") (pin "1") (pinfunction "1_1") (pintype "passive"))
      (node (ref "U5") (pin "4") (pinfunction "OUT+_4") (pintype "output"))
    )
    (net (code "242") (name "Net-(U5-OUT-)") (class "Default")
      (node (ref "C55") (pin "1") (pinfunction "1_1") (pintype "passive"))
      (node (ref "R15") (pin "2") (pinfunction "2_2") (pintype "passive"))
      (node (ref "U5") (pin "5") (pinfunction "OUT-_5") (pintype "output"))
    )
    (net (code "243") (name "PROG_B") (class "Default")
      (node (ref "JM1") (pin "94") (pinfunction "94_94") (pintype "bidirectional"))
    )
    (net (code "244") (name "SCL") (class "Default")
      (node (ref "PCIE-NORTH") (pin "B2") (pinfunction "SCL_B2") (pintype "passive"))
      (node (ref "U1") (pin "6") (pinfunction "SCL_6") (pintype "input"))
    )
    (net (code "245") (name "SDA") (class "Default")
      (node (ref "PCIE-NORTH") (pin "B1") (pinfunction "SDA_B1") (pintype "passive"))
      (node (ref "U1") (pin "5") (pinfunction "SDA_5") (pintype "bidirectional"))
    )
    (net (code "246") (name "SPI-CLK") (class "Default")
      (node (ref "JM2") (pin "67") (pinfunction "67_67") (pintype "bidirectional"))
    )
    (net (code "247") (name "SPI-CS") (class "Default")
      (node (ref "JM2") (pin "69") (pinfunction "69_69") (pintype "bidirectional"))
    )
    (net (code "248") (name "SPI-DQ0") (class "Default")
      (node (ref "JM2") (pin "68") (pinfunction "68_68") (pintype "bidirectional"))
    )
    (net (code "249") (name "SPI-DQ1") (class "Default")
      (node (ref "JM2") (pin "71") (pinfunction "71_71") (pintype "bidirectional"))
    )
    (net (code "250") (name "SPI-DQ2") (class "Default")
      (node (ref "JM2") (pin "73") (pinfunction "73_73") (pintype "bidirectional"))
    )
    (net (code "251") (name "SPI-DQ3") (class "Default")
      (node (ref "JM2") (pin "70") (pinfunction "70_70") (pintype "bidirectional"))
    )
    (net (code "252") (name "S_5V") (class "Default")
      (node (ref "PCIE-SOUTH") (pin "B12") (pinfunction "5V_B12") (pintype "passive"))
    )
    (net (code "253") (name "S_PCIE_V") (class "Default")
      (node (ref "PCIE-SOUTH") (pin "B13") (pinfunction "VCC_B13") (pintype "passive"))
    )
    (net (code "254") (name "S_VCCIO") (class "Default")
      (node (ref "PCIE-SOUTH") (pin "B14") (pinfunction "VCCIO_B14") (pintype "passive"))
    )
    (net (code "255") (name "TCK") (class "Default")
      (node (ref "JM1") (pin "90") (pinfunction "90_90") (pintype "bidirectional"))
    )
    (net (code "256") (name "TDI") (class "Default")
      (node (ref "JM1") (pin "86") (pinfunction "86_86") (pintype "bidirectional"))
    )
    (net (code "257") (name "TDO") (class "Default")
      (node (ref "JM1") (pin "88") (pinfunction "88_88") (pintype "bidirectional"))
    )
    (net (code "258") (name "TMS") (class "Default")
      (node (ref "JM1") (pin "92") (pinfunction "92_92") (pintype "bidirectional"))
    )
    (net (code "259") (name "VCCIO0") (class "Default")
      (node (ref "JM2") (pin "53") (pinfunction "53_53") (pintype "bidirectional"))
    )
    (net (code "260") (name "VCCIO15") (class "Default")
      (node (ref "JM2") (pin "54") (pinfunction "54_54") (pintype "bidirectional"))
    )
    (net (code "261") (name "VCCIO34") (class "Default")
      (node (ref "JM1") (pin "61") (pinfunction "61_61") (pintype "bidirectional"))
    )
    (net (code "262") (name "VCCO_4") (class "Default")
      (node (ref "C14") (pin "1") (pinfunction "1_1") (pintype "passive"))
      (node (ref "C15") (pin "1") (pinfunction "1_1") (pintype "passive"))
      (node (ref "C16") (pin "1") (pinfunction "1_1") (pintype "passive"))
      (node (ref "FB3") (pin "2") (pinfunction "2_2") (pintype "passive"))
      (node (ref "U2") (pin "24") (pinfunction "VCCO_1_24") (pintype "power_in"))
      (node (ref "U2") (pin "25") (pinfunction "VCCO_0_25") (pintype "power_in"))
    )
    (net (code "263") (name "VCCO_8") (class "Default")
      (node (ref "C32") (pin "1") (pinfunction "1_1") (pintype "passive"))
      (node (ref "C33") (pin "1") (pinfunction "1_1") (pintype "passive"))
      (node (ref "C34") (pin "1") (pinfunction "1_1") (pintype "passive"))
      (node (ref "FB6") (pin "2") (pinfunction "2_2") (pintype "passive"))
      (node (ref "U3") (pin "24") (pinfunction "VCCO_1_24") (pintype "power_in"))
      (node (ref "U3") (pin "25") (pinfunction "VCCO_0_25") (pintype "power_in"))
    )
    (net (code "264") (name "VCCO_9") (class "Default")
      (node (ref "C50") (pin "1") (pinfunction "1_1") (pintype "passive"))
      (node (ref "C51") (pin "1") (pinfunction "1_1") (pintype "passive"))
      (node (ref "C52") (pin "1") (pinfunction "1_1") (pintype "passive"))
      (node (ref "FB9") (pin "2") (pinfunction "2_2") (pintype "passive"))
      (node (ref "U4") (pin "24") (pinfunction "VCCO_1_24") (pintype "power_in"))
      (node (ref "U4") (pin "25") (pinfunction "VCCO_0_25") (pintype "power_in"))
    )
    (net (code "265") (name "VCC_4") (class "Default")
      (node (ref "C11") (pin "1") (pinfunction "1_1") (pintype "passive"))
      (node (ref "C12") (pin "1") (pinfunction "1_1") (pintype "passive"))
      (node (ref "C13") (pin "1") (pinfunction "1_1") (pintype "passive"))
      (node (ref "FB2") (pin "2") (pinfunction "2_2") (pintype "passive"))
      (node (ref "U2") (pin "35") (pinfunction "VCC_CORE_35") (pintype "power_in"))
      (node (ref "U2") (pin "4") (pinfunction "VCC_SDI_4") (pintype "power_in"))
    )
    (net (code "266") (name "VCC_8") (class "Default")
      (node (ref "C29") (pin "1") (pinfunction "1_1") (pintype "passive"))
      (node (ref "C30") (pin "1") (pinfunction "1_1") (pintype "passive"))
      (node (ref "C31") (pin "1") (pinfunction "1_1") (pintype "passive"))
      (node (ref "FB5") (pin "2") (pinfunction "2_2") (pintype "passive"))
      (node (ref "U3") (pin "35") (pinfunction "VCC_CORE_35") (pintype "power_in"))
      (node (ref "U3") (pin "4") (pinfunction "VCC_DDI_4") (pintype "power_in"))
    )
    (net (code "267") (name "VCC_9") (class "Default")
      (node (ref "C47") (pin "1") (pinfunction "1_1") (pintype "passive"))
      (node (ref "C48") (pin "1") (pinfunction "1_1") (pintype "passive"))
      (node (ref "C49") (pin "1") (pinfunction "1_1") (pintype "passive"))
      (node (ref "FB8") (pin "2") (pinfunction "2_2") (pintype "passive"))
      (node (ref "U4") (pin "35") (pinfunction "VCC_CORE_35") (pintype "power_in"))
      (node (ref "U4") (pin "4") (pinfunction "VCC_DDI_4") (pintype "power_in"))
    )
    (net (code "268") (name "VDD_4") (class "Default")
      (node (ref "C10") (pin "1") (pinfunction "1_1") (pintype "passive"))
      (node (ref "C7") (pin "1") (pinfunction "1_1") (pintype "passive"))
      (node (ref "C8") (pin "1") (pinfunction "1_1") (pintype "passive"))
      (node (ref "C9") (pin "1") (pinfunction "1_1") (pintype "passive"))
      (node (ref "FB1") (pin "2") (pinfunction "2_2") (pintype "passive"))
      (node (ref "U2") (pin "16") (pinfunction "VDD_16") (pintype "power_in"))
      (node (ref "U2") (pin "20") (pinfunction "VCCO1V8_1_20") (pintype "power_in"))
      (node (ref "U2") (pin "29") (pinfunction "VCCO1V8_0_29") (pintype "power_in"))
    )
    (net (code "269") (name "VDD_8") (class "Default")
      (node (ref "C25") (pin "1") (pinfunction "1_1") (pintype "passive"))
      (node (ref "C26") (pin "1") (pinfunction "1_1") (pintype "passive"))
      (node (ref "C27") (pin "1") (pinfunction "1_1") (pintype "passive"))
      (node (ref "C28") (pin "1") (pinfunction "1_1") (pintype "passive"))
      (node (ref "FB4") (pin "2") (pinfunction "2_2") (pintype "passive"))
      (node (ref "U3") (pin "16") (pinfunction "VDD_16") (pintype "power_in"))
      (node (ref "U3") (pin "20") (pinfunction "VCCO1V8_1_20") (pintype "power_in"))
      (node (ref "U3") (pin "29") (pinfunction "VCCO1V8_0_29") (pintype "power_in"))
    )
    (net (code "270") (name "VDD_9") (class "Default")
      (node (ref "C43") (pin "1") (pinfunction "1_1") (pintype "passive"))
      (node (ref "C44") (pin "1") (pinfunction "1_1") (pintype "passive"))
      (node (ref "C45") (pin "1") (pinfunction "1_1") (pintype "passive"))
      (node (ref "C46") (pin "1") (pinfunction "1_1") (pintype "passive"))
      (node (ref "FB7") (pin "2") (pinfunction "2_2") (pintype "passive"))
      (node (ref "U4") (pin "16") (pinfunction "VDD_16") (pintype "power_in"))
      (node (ref "U4") (pin "20") (pinfunction "VCCO1V8_1_20") (pintype "power_in"))
      (node (ref "U4") (pin "29") (pinfunction "VCCO1V8_0_29") (pintype "power_in"))
    )
    (net (code "271") (name "VIN") (class "Default")
      (node (ref "JM1") (pin "97") (pinfunction "97_97") (pintype "bidirectional"))
      (node (ref "JM1") (pin "99") (pinfunction "99_99") (pintype "bidirectional"))
      (node (ref "JP2") (pin "2") (pinfunction "2_2") (pintype "passive"))
    )
    (net (code "272") (name "VSUP") (class "Default")
      (node (ref "JP2") (pin "3") (pinfunction "3_3") (pintype "passive"))
    )
    (net (code "273") (name "VXX") (class "Default")
      (node (ref "C53") (pin "1") (pinfunction "1_1") (pintype "passive"))
      (node (ref "L1") (pin "2") (pinfunction "2_2") (pintype "passive"))
      (node (ref "U5") (pin "6") (pinfunction "VCC_6") (pintype "power_in"))
    )
    (net (code "274") (name "unconnected-(JP1-Pad1)") (class "Default")
      (node (ref "JP1") (pin "1") (pinfunction "1_1") (pintype "passive"))
    )
    (net (code "275") (name "unconnected-(JP1-Pad2)") (class "Default")
      (node (ref "JP1") (pin "2") (pinfunction "2_2") (pintype "passive"))
    )
    (net (code "276") (name "unconnected-(JP1-Pad3)") (class "Default")
      (node (ref "JP1") (pin "3") (pinfunction "3_3") (pintype "passive"))
    )
    (net (code "277") (name "unconnected-(JP1-Pad4)") (class "Default")
      (node (ref "JP1") (pin "4") (pinfunction "4_4") (pintype "passive"))
    )
    (net (code "278") (name "unconnected-(JP1-Pad5)") (class "Default")
      (node (ref "JP1") (pin "5") (pinfunction "5_5") (pintype "passive"))
    )
    (net (code "279") (name "unconnected-(JP1-Pad6)") (class "Default")
      (node (ref "JP1") (pin "6") (pinfunction "6_6") (pintype "passive"))
    )
    (net (code "280") (name "unconnected-(JP1-Pad7)") (class "Default")
      (node (ref "JP1") (pin "7") (pinfunction "7_7") (pintype "passive"))
    )
    (net (code "281") (name "unconnected-(JP1-Pad8)") (class "Default")
      (node (ref "JP1") (pin "8") (pinfunction "8_8") (pintype "passive"))
    )
    (net (code "282") (name "unconnected-(JP1-Pad9)") (class "Default")
      (node (ref "JP1") (pin "9") (pinfunction "9_9") (pintype "passive"))
    )
    (net (code "283") (name "unconnected-(JP1-Pad10)") (class "Default")
      (node (ref "JP1") (pin "10") (pinfunction "10_10") (pintype "passive"))
    )
    (net (code "284") (name "unconnected-(JP1-Pad11)") (class "Default")
      (node (ref "JP1") (pin "11") (pinfunction "11_11") (pintype "passive"))
    )
    (net (code "285") (name "unconnected-(JP1-Pad12)") (class "Default")
      (node (ref "JP1") (pin "12") (pinfunction "12_12") (pintype "passive"))
    )
    (net (code "286") (name "unconnected-(JP1-Pad13)") (class "Default")
      (node (ref "JP1") (pin "13") (pinfunction "13_13") (pintype "passive"))
    )
    (net (code "287") (name "unconnected-(JP1-Pad14)") (class "Default")
      (node (ref "JP1") (pin "14") (pinfunction "14_14") (pintype "passive"))
    )
    (net (code "288") (name "unconnected-(PCIE-NORTH-PWRGD-PadA11)") (class "Default")
      (node (ref "PCIE-NORTH") (pin "A11") (pinfunction "PWRGD_A11") (pintype "passive"))
    )
    (net (code "289") (name "unconnected-(PCIE-SOUTH-PWRGD-PadA11)") (class "Default")
      (node (ref "PCIE-SOUTH") (pin "A11") (pinfunction "PWRGD_A11") (pintype "passive"))
    )
    (net (code "290") (name "unconnected-(PCIE-SOUTH-SCL-PadB2)") (class "Default")
      (node (ref "PCIE-SOUTH") (pin "B2") (pinfunction "SCL_B2") (pintype "passive"))
    )
    (net (code "291") (name "unconnected-(PCIE-SOUTH-SDA-PadB1)") (class "Default")
      (node (ref "PCIE-SOUTH") (pin "B1") (pinfunction "SDA_B1") (pintype "passive"))
    )
    (net (code "292") (name "unconnected-(PCIE-SOUTH-V_I2C-PadB3)") (class "Default")
      (node (ref "PCIE-SOUTH") (pin "B3") (pinfunction "V_I2C_B3") (pintype "passive"))
    )
  )
)
